# STM32F103-260914.net
KiCad netlist of a schematic drawn in EasyEDA Pro
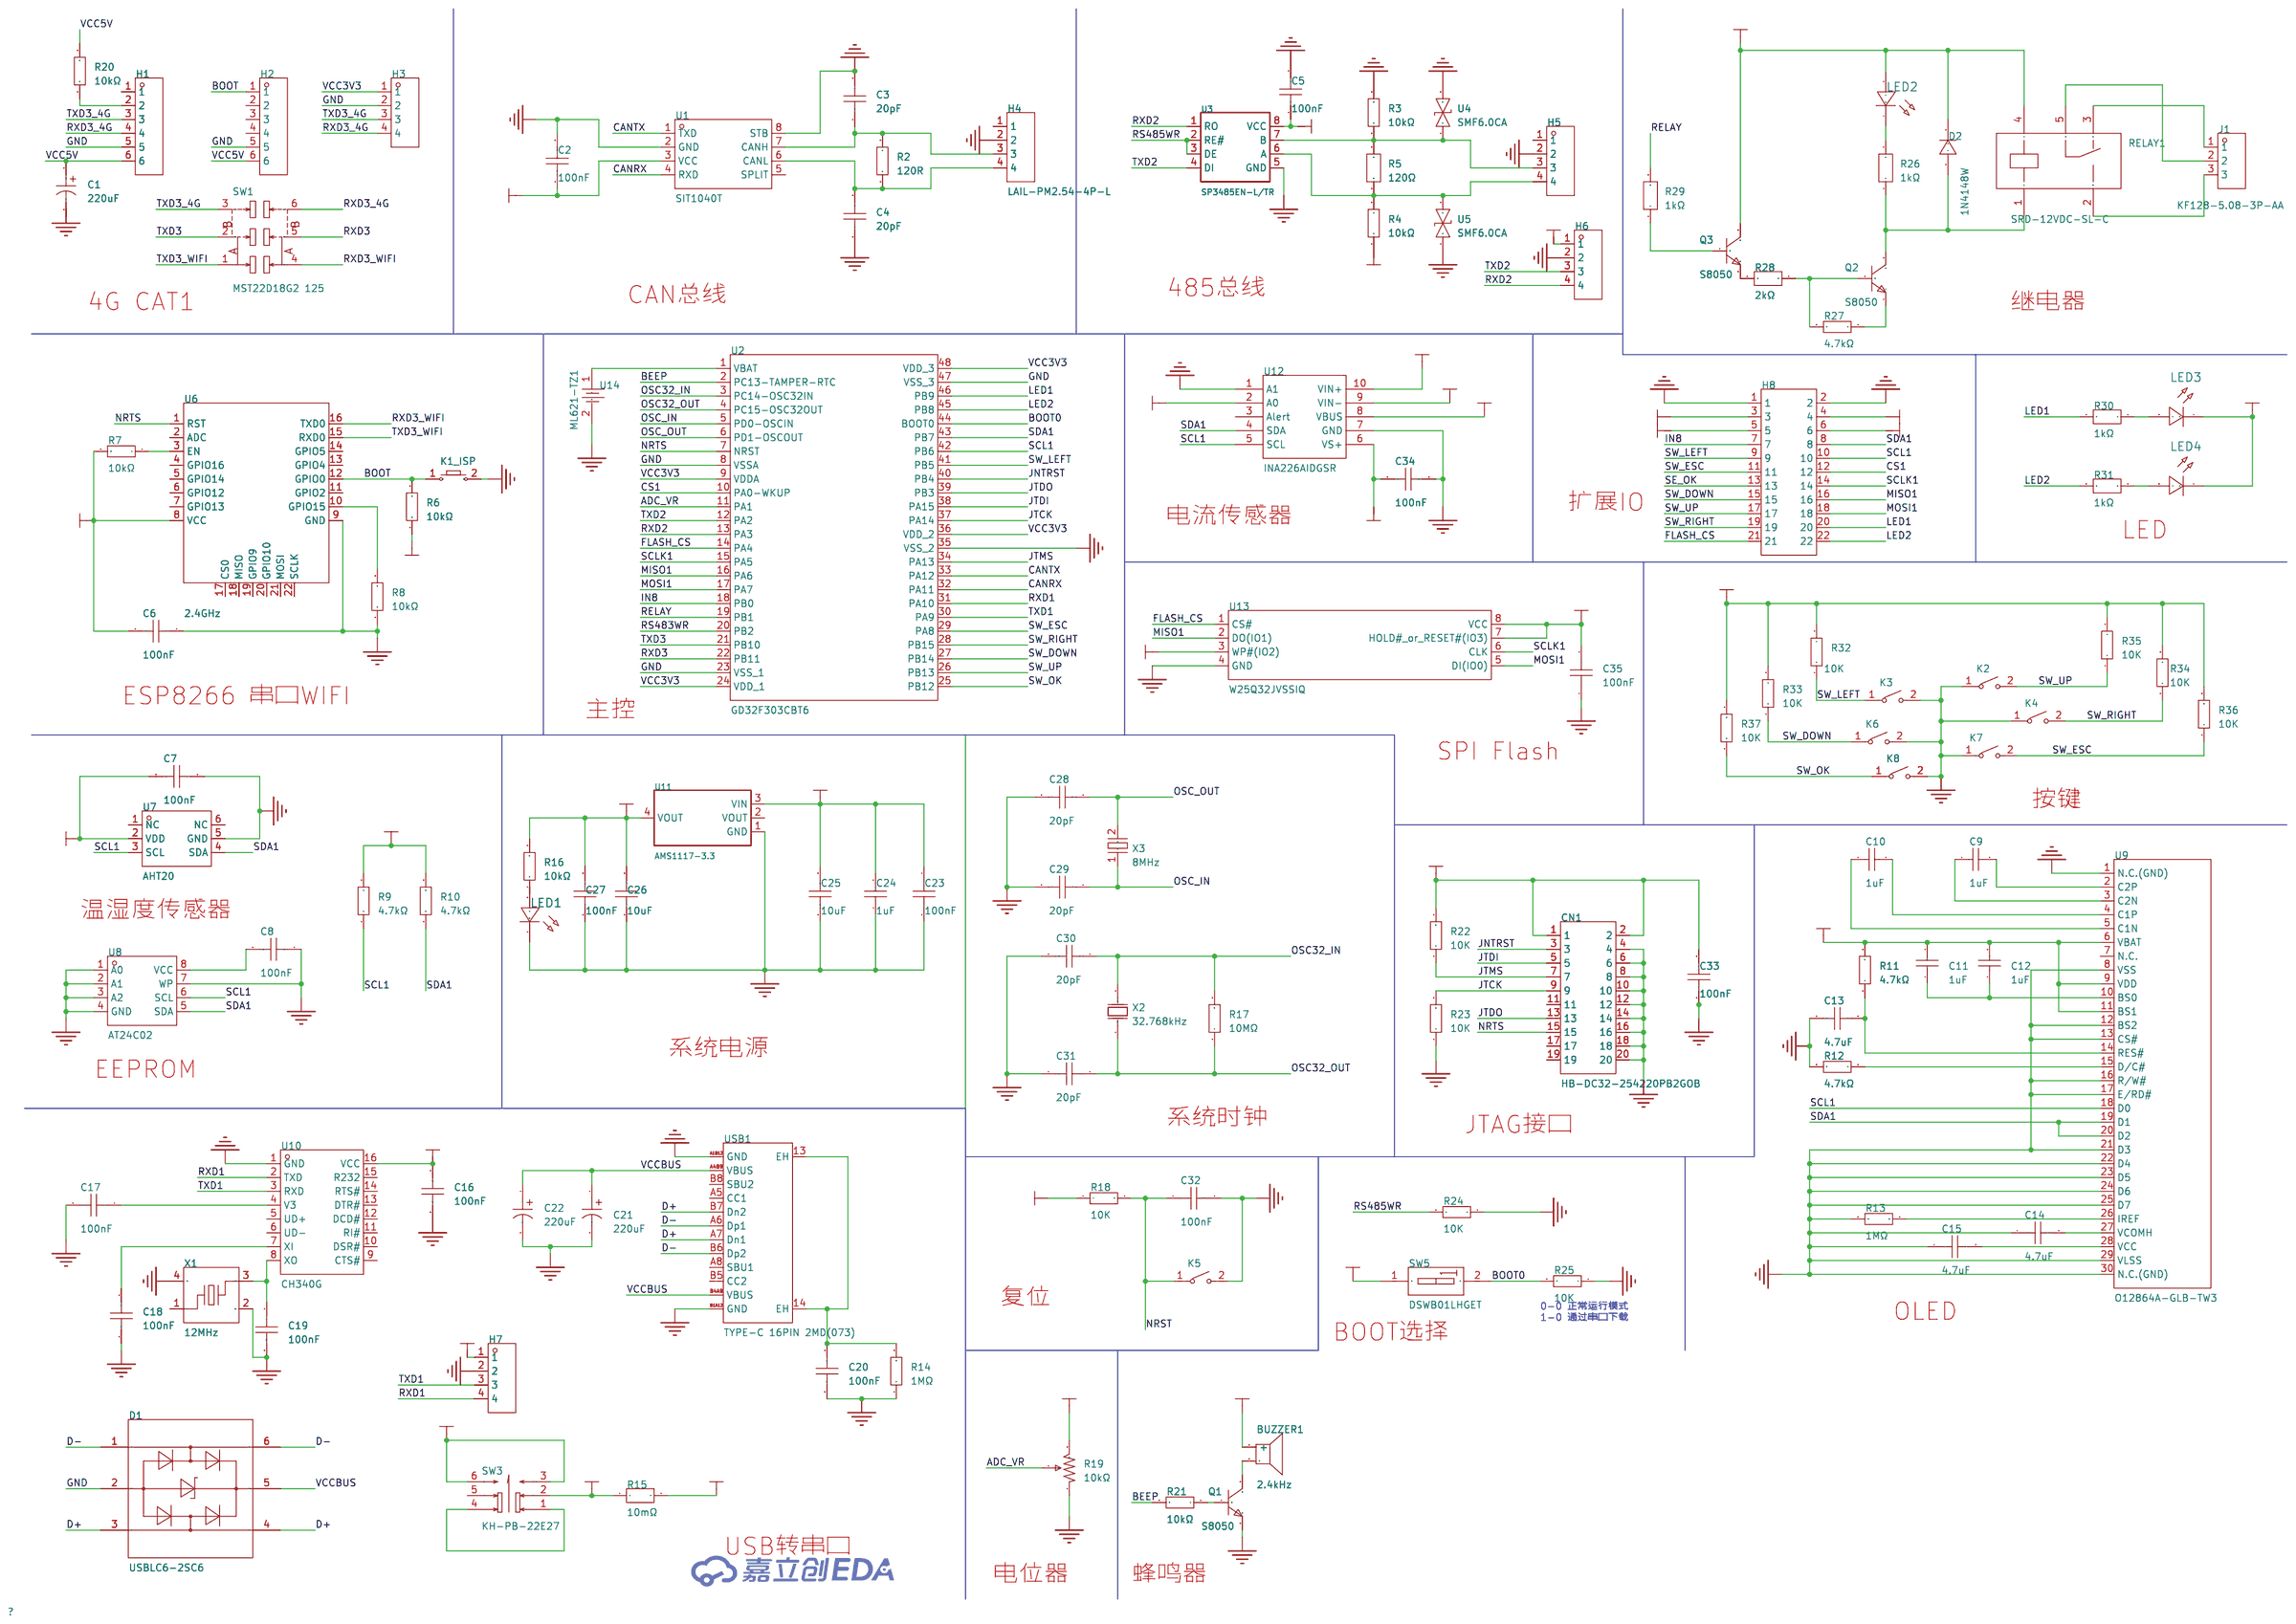
[diagram p0: schematic sheet]

(export (version "E")
  (design (tool "Eeschema 10.0.6"))
  (components
    (comp (ref "BUZZER1")
      (value "2.4kHz")
      (footprint "easyedapro:BUZ-TH_BD12.0-P7.60-D0.6-FD")
      (description "驱动方式:有源(内含驱动线路);构造类型:电磁式;额定电压:5V;频率:2.4kHz;声压(SPL):85dB;")
      (fields (field (name "Manufacturer Part") "TMB12A05") (field (name "Manufacturer") "华能"))
      (libsource (lib "easyedapro") (part "TMB12A05"))
    )
    (comp (ref "C1")
      (value "220uF")
      (footprint "easyedapro:CAP-SMD_BD6.3-L6.6-W6.6-FD")
      (description "容值:220uF;精度:±20%;额定电压:35V;纹波电流:190mA@120Hz;")
      (fields (field (name "Manufacturer Part") "JVJ35V220M6x8") (field (name "Manufacturer") "JIERR(捷而瑞)"))
      (libsource (lib "easyedapro") (part "JVJ35V220M6X8"))
    )
    (comp (ref "C2")
      (value "100nF")
      (footprint "easyedapro:C0805")
      (libsource (lib "easyedapro") (part "Capacitance"))
    )
    (comp (ref "C3")
      (value "20pF")
      (footprint "easyedapro:C0805")
      (libsource (lib "easyedapro") (part "Capacitance"))
    )
    (comp (ref "C4")
      (value "20pF")
      (footprint "easyedapro:C0805")
      (libsource (lib "easyedapro") (part "Capacitance"))
    )
    (comp (ref "C5")
      (value "100nF")
      (footprint "easyedapro:C0603")
      (description "容值:100nF;精度:±10%;额定电压:100V;温度系数:X7R;")
      (fields
        (field (name "Manufacturer Part") "CC0603KRX7R0BB104")
        (field (name "Manufacturer") "YAGEO(国巨)")
      )
      (libsource (lib "easyedapro") (part "CC0603KRX7R0BB104"))
    )
    (comp (ref "C6")
      (value "100nF")
      (footprint "easyedapro:C0603")
      (description "容值:100nF;精度:±10%;额定电压:100V;温度系数:X7R;")
      (fields
        (field (name "Manufacturer Part") "CC0603KRX7R0BB104")
        (field (name "Manufacturer") "YAGEO(国巨)")
      )
      (libsource (lib "easyedapro") (part "CC0603KRX7R0BB104"))
    )
    (comp (ref "C7")
      (value "100nF")
      (footprint "easyedapro:C0603")
      (description "容值:100nF;精度:±10%;额定电压:100V;温度系数:X7R;")
      (fields
        (field (name "Manufacturer Part") "CC0603KRX7R0BB104")
        (field (name "Manufacturer") "YAGEO(国巨)")
      )
      (libsource (lib "easyedapro") (part "CC0603KRX7R0BB104"))
    )
    (comp (ref "C8")
      (value "100nF")
      (footprint "easyedapro:C0603")
      (description "容值:100nF;精度:±10%;额定电压:100V;温度系数:X7R;")
      (fields
        (field (name "Manufacturer Part") "CC0603KRX7R0BB104")
        (field (name "Manufacturer") "YAGEO(国巨)")
      )
      (libsource (lib "easyedapro") (part "CC0603KRX7R0BB104"))
    )
    (comp (ref "C9")
      (value "1uF")
      (footprint "easyedapro:C0603")
      (description "容值:1uF;精度:±10%;额定电压:25V;温度系数:X5R;")
      (fields
        (field (name "Manufacturer Part") "CC0603KRX5R8BB105")
        (field (name "Manufacturer") "YAGEO(国巨)")
      )
      (libsource (lib "easyedapro") (part "CC0603KRX5R8BB105"))
    )
    (comp (ref "C10")
      (value "1uF")
      (footprint "easyedapro:C0603")
      (description "容值:1uF;精度:±10%;额定电压:25V;温度系数:X5R;")
      (fields
        (field (name "Manufacturer Part") "CC0603KRX5R8BB105")
        (field (name "Manufacturer") "YAGEO(国巨)")
      )
      (libsource (lib "easyedapro") (part "CC0603KRX5R8BB105"))
    )
    (comp (ref "C11")
      (value "1uF")
      (footprint "easyedapro:C0603")
      (description "容值:1uF;精度:±10%;额定电压:25V;温度系数:X5R;")
      (fields
        (field (name "Manufacturer Part") "CC0603KRX5R8BB105")
        (field (name "Manufacturer") "YAGEO(国巨)")
      )
      (libsource (lib "easyedapro") (part "CC0603KRX5R8BB105"))
    )
    (comp (ref "C12")
      (value "1uF")
      (footprint "easyedapro:C0603")
      (description "容值:1uF;精度:±10%;额定电压:25V;温度系数:X5R;")
      (fields
        (field (name "Manufacturer Part") "CC0603KRX5R8BB105")
        (field (name "Manufacturer") "YAGEO(国巨)")
      )
      (libsource (lib "easyedapro") (part "CC0603KRX5R8BB105"))
    )
    (comp (ref "C13")
      (value "4.7uF")
      (footprint "easyedapro:C0603")
      (description "容值:4.7uF;精度:±10%;额定电压:16V;温度系数:X5R;")
      (fields
        (field (name "Manufacturer Part") "CL10A475KO8NNNC")
        (field (name "Manufacturer") "SAMSUNG(三星)")
      )
      (libsource (lib "easyedapro") (part "CL10A475KO8NNNC"))
    )
    (comp (ref "C14")
      (value "4.7uF")
      (footprint "easyedapro:C0603")
      (description "容值:4.7uF;精度:±10%;额定电压:16V;温度系数:X5R;")
      (fields
        (field (name "Manufacturer Part") "CL10A475KO8NNNC")
        (field (name "Manufacturer") "SAMSUNG(三星)")
      )
      (libsource (lib "easyedapro") (part "CL10A475KO8NNNC"))
    )
    (comp (ref "C15")
      (value "4.7uF")
      (footprint "easyedapro:C0603")
      (description "容值:4.7uF;精度:±10%;额定电压:16V;温度系数:X5R;")
      (fields
        (field (name "Manufacturer Part") "CL10A475KO8NNNC")
        (field (name "Manufacturer") "SAMSUNG(三星)")
      )
      (libsource (lib "easyedapro") (part "CL10A475KO8NNNC"))
    )
    (comp (ref "C16")
      (value "100nF")
      (footprint "easyedapro:C0603")
      (description "容值:100nF;精度:±10%;额定电压:100V;温度系数:X7R;")
      (fields
        (field (name "Manufacturer Part") "CC0603KRX7R0BB104")
        (field (name "Manufacturer") "YAGEO(国巨)")
      )
      (libsource (lib "easyedapro") (part "CC0603KRX7R0BB104"))
    )
    (comp (ref "C17")
      (value "100nF")
      (footprint "easyedapro:C0603")
      (description "容值:100nF;精度:±10%;额定电压:100V;温度系数:X7R;")
      (fields
        (field (name "Manufacturer Part") "CC0603KRX7R0BB104")
        (field (name "Manufacturer") "YAGEO(国巨)")
      )
      (libsource (lib "easyedapro") (part "CC0603KRX7R0BB104"))
    )
    (comp (ref "C18")
      (value "100nF")
      (footprint "easyedapro:C0603")
      (description "容值:100nF;精度:±10%;额定电压:100V;温度系数:X7R;")
      (fields
        (field (name "Manufacturer Part") "CC0603KRX7R0BB104")
        (field (name "Manufacturer") "YAGEO(国巨)")
      )
      (libsource (lib "easyedapro") (part "CC0603KRX7R0BB104"))
    )
    (comp (ref "C19")
      (value "100nF")
      (footprint "easyedapro:C0603")
      (description "容值:100nF;精度:±10%;额定电压:100V;温度系数:X7R;")
      (fields
        (field (name "Manufacturer Part") "CC0603KRX7R0BB104")
        (field (name "Manufacturer") "YAGEO(国巨)")
      )
      (libsource (lib "easyedapro") (part "CC0603KRX7R0BB104"))
    )
    (comp (ref "C20")
      (value "100nF")
      (footprint "easyedapro:C0603")
      (description "容值:100nF;精度:±10%;额定电压:100V;温度系数:X7R;")
      (fields
        (field (name "Manufacturer Part") "CC0603KRX7R0BB104")
        (field (name "Manufacturer") "YAGEO(国巨)")
      )
      (libsource (lib "easyedapro") (part "CC0603KRX7R0BB104"))
    )
    (comp (ref "C21")
      (value "220uF")
      (footprint "easyedapro:CAP-SMD_BD6.3-L6.6-W6.6-FD")
      (description "容值:220uF;精度:±20%;额定电压:35V;纹波电流:600mA@100kHz;等效串联电阻(ESR):160mΩ@100kHz;")
      (fields (field (name "Manufacturer Part") "189RV0019") (field (name "Manufacturer") "KNSCHA(科尼盛)"))
      (libsource (lib "easyedapro") (part "189RV0019"))
    )
    (comp (ref "C22")
      (value "220uF")
      (footprint "easyedapro:CAP-SMD_BD6.3-L6.6-W6.6-FD")
      (description "容值:220uF;精度:±20%;额定电压:35V;纹波电流:600mA@100kHz;等效串联电阻(ESR):160mΩ@100kHz;")
      (fields (field (name "Manufacturer Part") "189RV0019") (field (name "Manufacturer") "KNSCHA(科尼盛)"))
      (libsource (lib "easyedapro") (part "189RV0019"))
    )
    (comp (ref "C23")
      (value "100nF")
      (footprint "easyedapro:C0603")
      (description "容值:100nF;精度:±10%;额定电压:100V;温度系数:X7R;")
      (fields
        (field (name "Manufacturer Part") "CC0603KRX7R0BB104")
        (field (name "Manufacturer") "YAGEO(国巨)")
      )
      (libsource (lib "easyedapro") (part "CC0603KRX7R0BB104"))
    )
    (comp (ref "C24")
      (value "1uF")
      (footprint "easyedapro:C0603")
      (description "容值:1uF;精度:±10%;额定电压:25V;温度系数:X5R;")
      (fields
        (field (name "Manufacturer Part") "CC0603KRX5R8BB105")
        (field (name "Manufacturer") "YAGEO(国巨)")
      )
      (libsource (lib "easyedapro") (part "CC0603KRX5R8BB105"))
    )
    (comp (ref "C25")
      (value "10uF")
      (footprint "easyedapro:C0603")
      (description "容值:10uF;精度:±20%;额定电压:25V;温度系数:X5R;")
      (fields
        (field (name "Manufacturer Part") "CL10A106MA8NRNC")
        (field (name "Manufacturer") "SAMSUNG(三星)")
      )
      (libsource (lib "easyedapro") (part "CL10A106MA8NRNC"))
    )
    (comp (ref "C26")
      (value "10uF")
      (footprint "easyedapro:C0603")
      (description "容值:10uF;精度:±20%;额定电压:25V;温度系数:X5R;")
      (fields
        (field (name "Manufacturer Part") "CL10A106MA8NRNC")
        (field (name "Manufacturer") "SAMSUNG(三星)")
      )
      (libsource (lib "easyedapro") (part "CL10A106MA8NRNC"))
    )
    (comp (ref "C27")
      (value "100nF")
      (footprint "easyedapro:C0603")
      (description "容值:100nF;精度:±10%;额定电压:100V;温度系数:X7R;")
      (fields
        (field (name "Manufacturer Part") "CC0603KRX7R0BB104")
        (field (name "Manufacturer") "YAGEO(国巨)")
      )
      (libsource (lib "easyedapro") (part "CC0603KRX7R0BB104"))
    )
    (comp (ref "C28")
      (value "20pF")
      (footprint "easyedapro:C0805")
      (libsource (lib "easyedapro") (part "Capacitance"))
    )
    (comp (ref "C29")
      (value "20pF")
      (footprint "easyedapro:C0805")
      (libsource (lib "easyedapro") (part "Capacitance"))
    )
    (comp (ref "C30")
      (value "20pF")
      (footprint "easyedapro:C0805")
      (libsource (lib "easyedapro") (part "Capacitance"))
    )
    (comp (ref "C31")
      (value "20pF")
      (footprint "easyedapro:C0805")
      (libsource (lib "easyedapro") (part "Capacitance"))
    )
    (comp (ref "C32")
      (value "100nF")
      (footprint "easyedapro:C0603")
      (description "容值:100nF;精度:±10%;额定电压:100V;温度系数:X7R;")
      (fields
        (field (name "Manufacturer Part") "CC0603KRX7R0BB104")
        (field (name "Manufacturer") "YAGEO(国巨)")
      )
      (libsource (lib "easyedapro") (part "CC0603KRX7R0BB104"))
    )
    (comp (ref "C33")
      (value "100nF")
      (footprint "easyedapro:C0603")
      (description "容值:100nF;精度:±10%;额定电压:100V;温度系数:X7R;")
      (fields
        (field (name "Manufacturer Part") "CC0603KRX7R0BB104")
        (field (name "Manufacturer") "YAGEO(国巨)")
      )
      (libsource (lib "easyedapro") (part "CC0603KRX7R0BB104"))
    )
    (comp (ref "C34")
      (value "100nF")
      (footprint "easyedapro:C0603")
      (description "容值:100nF;精度:±10%;额定电压:100V;温度系数:X7R;")
      (fields
        (field (name "Manufacturer Part") "CC0603KRX7R0BB104")
        (field (name "Manufacturer") "YAGEO(国巨)")
      )
      (libsource (lib "easyedapro") (part "CC0603KRX7R0BB104"))
    )
    (comp (ref "C35")
      (value "100nF")
      (footprint "easyedapro:C0603")
      (description "容值:100nF;精度:±10%;额定电压:100V;温度系数:X7R;")
      (fields
        (field (name "Manufacturer Part") "CC0603KRX7R0BB104")
        (field (name "Manufacturer") "YAGEO(国巨)")
      )
      (libsource (lib "easyedapro") (part "CC0603KRX7R0BB104"))
    )
    (comp (ref "CN1")
      (value "HB-DC32-254220PB2GOB")
      (footprint "easyedapro:CONN-TH-20P_HB-DC32-254220PB2GOB")
      (fields (field (name "Manufacturer") "HANBO(汉博)"))
      (libsource (lib "easyedapro") (part "HB-DC32-254220PB2GOB"))
    )
    (comp (ref "D1")
      (value "USBLC6-2SC6")
      (footprint "easyedapro:SOT-23-6_L2.9-W1.6-P0.95-LS2.8-BL")
      (description "极性:单向;反向截止电压(Vrwm):5.25V;钳位电压:17V;峰值脉冲电流(Ipp):5A;击穿电压(VBR):6V;")
      (fields (field (name "Manufacturer") "ST(意法半导体)"))
      (libsource (lib "easyedapro") (part "USBLC6-2SC6"))
    )
    (comp (ref "D2")
      (value "1N4148W")
      (footprint "easyedapro:SOD-123F_L2.7-W1.6-LS3.8-RD")
      (description "二极管配置:独立式;正向压降(Vf):1V@50mA;直流反向耐压(Vr):75V;整流电流:150mA;反向恢复时间(Trr):4ns;")
      (fields (field (name "Manufacturer") "ST(先科)"))
      (libsource (lib "easyedapro") (part "1N4148W_C81598"))
    )
    (comp (ref "H1")
      (value "~")
      (footprint "easyedapro:HDR-TH_6P-P2.54-V-F")
      (libsource (lib "easyedapro") (part "Header-Female-2.54_1x6"))
    )
    (comp (ref "H2")
      (value "~")
      (footprint "easyedapro:HDR-TH_6P-P2.54-V-F")
      (libsource (lib "easyedapro") (part "Header-Female-2.54_1x6"))
    )
    (comp (ref "H3")
      (value "~")
      (footprint "easyedapro:HDR-TH_4P-P2.54-V-F")
      (libsource (lib "easyedapro") (part "2.54-1*4P母"))
    )
    (comp (ref "H4")
      (value "LAIL-PM2.54-4P-L")
      (footprint "easyedapro:HDR-TH_4P-P2.54-V-M")
      (fields (field (name "Manufacturer") "LAILAN(莱联)"))
      (libsource (lib "easyedapro") (part "PZ254V-11-04P"))
    )
    (comp (ref "H5")
      (value "PM254V-11-04-H85")
      (footprint "easyedapro:HDR-TH_4P-P2.54-V-F")
      (fields (field (name "Manufacturer") "XFCN(兴飞)"))
      (libsource (lib "easyedapro") (part "2.54-1*4P母"))
    )
    (comp (ref "H6")
      (value "~")
      (footprint "easyedapro:HDR-TH_4P-P2.54-V-F")
      (libsource (lib "easyedapro") (part "2.54-1*4P母"))
    )
    (comp (ref "H7")
      (value "~")
      (footprint "easyedapro:HDR-TH_4P-P2.54-V-F")
      (libsource (lib "easyedapro") (part "2.54-1*4P母"))
    )
    (comp (ref "H8")
      (value "PZ254V-12-22P")
      (footprint "easyedapro:HDR-TH_22P-P2.54-V-M-R2-C11-S2.54")
      (fields (field (name "Manufacturer") "XFCN(兴飞)"))
      (libsource (lib "easyedapro") (part "PZ254V-12-22P"))
    )
    (comp (ref "J1")
      (value "KF128-5.08-3P-AA")
      (footprint "easyedapro:CONN-TH_3P-P5.08_KF128-5.08-3P")
      (fields (field (name "Manufacturer") "KEFA(科发)"))
      (libsource (lib "easyedapro") (part "KF128-5.08-3P"))
    )
    (comp (ref "K1_ISP")
      (value "KH-6X6X5H-STM")
      (footprint "easyedapro:Key_SMD_3x4x2")
      (fields (field (name "Manufacturer") "kinghelm(金航标)"))
      (libsource (lib "easyedapro") (part "轻触按键x2"))
    )
    (comp (ref "K2")
      (value "TS-1088R-02026")
      (footprint "easyedapro:SW-SMD_L3.9-W3.0-P4.45")
      (fields (field (name "Manufacturer") "XUNPU(讯普)"))
      (libsource (lib "easyedapro") (part "TS-1088R-02026"))
    )
    (comp (ref "K3")
      (value "TS-1088R-02026")
      (footprint "easyedapro:SW-SMD_L3.9-W3.0-P4.45")
      (fields (field (name "Manufacturer") "XUNPU(讯普)"))
      (libsource (lib "easyedapro") (part "TS-1088R-02026"))
    )
    (comp (ref "K4")
      (value "TS-1088R-02026")
      (footprint "easyedapro:SW-SMD_L3.9-W3.0-P4.45")
      (fields (field (name "Manufacturer") "XUNPU(讯普)"))
      (libsource (lib "easyedapro") (part "TS-1088R-02026"))
    )
    (comp (ref "K5")
      (value "TS-1088R-02026")
      (footprint "easyedapro:SW-SMD_L3.9-W3.0-P4.45")
      (fields (field (name "Manufacturer") "XUNPU(讯普)"))
      (libsource (lib "easyedapro") (part "TS-1088R-02026"))
    )
    (comp (ref "K6")
      (value "TS-1088R-02026")
      (footprint "easyedapro:SW-SMD_L3.9-W3.0-P4.45")
      (fields (field (name "Manufacturer") "XUNPU(讯普)"))
      (libsource (lib "easyedapro") (part "TS-1088R-02026"))
    )
    (comp (ref "K7")
      (value "TS-1088R-02026")
      (footprint "easyedapro:SW-SMD_L3.9-W3.0-P4.45")
      (fields (field (name "Manufacturer") "XUNPU(讯普)"))
      (libsource (lib "easyedapro") (part "TS-1088R-02026"))
    )
    (comp (ref "K8")
      (value "TS-1088R-02026")
      (footprint "easyedapro:SW-SMD_L3.9-W3.0-P4.45")
      (fields (field (name "Manufacturer") "XUNPU(讯普)"))
      (libsource (lib "easyedapro") (part "TS-1088R-02026"))
    )
    (comp (ref "LED1")
      (value "~")
      (footprint "easyedapro:LED_0603")
      (libsource (lib "easyedapro") (part "LED_R"))
    )
    (comp (ref "LED2")
      (value "~")
      (footprint "easyedapro:LED_0603")
      (libsource (lib "easyedapro") (part "LED_R"))
    )
    (comp (ref "LED3")
      (value "~")
      (footprint "easyedapro:LED_0603")
      (libsource (lib "easyedapro") (part "LED_R"))
    )
    (comp (ref "LED4")
      (value "~")
      (footprint "easyedapro:LED_0603")
      (libsource (lib "easyedapro") (part "LED_R"))
    )
    (comp (ref "Q1")
      (value "S8050")
      (footprint "easyedapro:SOT-23-3_L2.9-W1.3-P1.90-LS2.3-BR")
      (description "晶体管类型:NPN;集电极电流(Ic):500mA;集射极击穿电压(Vceo):25V;耗散功率(Pd):300mW;直流电流增益(hFE):120;")
      (fields (field (name "Manufacturer") "R+O(宏嘉诚)"))
      (libsource (lib "easyedapro") (part "S8050_C20069125"))
    )
    (comp (ref "Q2")
      (value "S8050")
      (footprint "easyedapro:SOT-23-3_L2.9-W1.3-P1.90-LS2.3-BR")
      (description "晶体管类型:NPN;集电极电流(Ic):500mA;集射极击穿电压(Vceo):25V;耗散功率(Pd):300mW;直流电流增益(hFE):120;")
      (fields (field (name "Manufacturer") "R+O(宏嘉诚)"))
      (libsource (lib "easyedapro") (part "S8050_C20069125"))
    )
    (comp (ref "Q3")
      (value "S8050")
      (footprint "easyedapro:SOT-23-3_L2.9-W1.3-P1.90-LS2.3-BR")
      (description "晶体管类型:NPN;集电极电流(Ic):500mA;集射极击穿电压(Vceo):25V;耗散功率(Pd):300mW;直流电流增益(hFE):120;")
      (fields (field (name "Manufacturer") "R+O(宏嘉诚)"))
      (libsource (lib "easyedapro") (part "S8050_C20069125"))
    )
    (comp (ref "R2") (value "120R") (footprint "easyedapro:R0805") (libsource (lib "easyedapro") (part "电阻")))
    (comp (ref "R3")
      (value "10kΩ")
      (footprint "easyedapro:R0603")
      (description "电阻类型:厚膜电阻;阻值:10kΩ;精度:±1%;功率:100mW;工作电压:75V;温度系数:±100ppm/°C;")
      (fields
        (field (name "Manufacturer Part") "0603WAF1002T5E")
        (field (name "Manufacturer") "UNI-ROYAL(厚声)")
      )
      (libsource (lib "easyedapro") (part "0603WAF1002T5E"))
    )
    (comp (ref "R4")
      (value "10kΩ")
      (footprint "easyedapro:R0603")
      (description "电阻类型:厚膜电阻;阻值:10kΩ;精度:±1%;功率:100mW;工作电压:75V;温度系数:±100ppm/°C;")
      (fields
        (field (name "Manufacturer Part") "0603WAF1002T5E")
        (field (name "Manufacturer") "UNI-ROYAL(厚声)")
      )
      (libsource (lib "easyedapro") (part "0603WAF1002T5E"))
    )
    (comp (ref "R5")
      (value "120Ω")
      (footprint "easyedapro:R1206")
      (description "电阻类型:厚膜电阻;阻值:120Ω;精度:±1%;功率:250mW;工作电压:200V;温度系数:±100ppm/°C;")
      (fields (field (name "Manufacturer Part") "FRC1206F1200TS") (field (name "Manufacturer") "FOJAN(富捷)"))
      (libsource (lib "easyedapro") (part "FRC1206F1200TS"))
    )
    (comp (ref "R6")
      (value "10kΩ")
      (footprint "easyedapro:R0603")
      (description "电阻类型:厚膜电阻;阻值:10kΩ;精度:±1%;功率:100mW;工作电压:75V;温度系数:±100ppm/°C;")
      (fields
        (field (name "Manufacturer Part") "0603WAF1002T5E")
        (field (name "Manufacturer") "UNI-ROYAL(厚声)")
      )
      (libsource (lib "easyedapro") (part "0603WAF1002T5E"))
    )
    (comp (ref "R7")
      (value "10kΩ")
      (footprint "easyedapro:R0603")
      (description "电阻类型:厚膜电阻;阻值:10kΩ;精度:±1%;功率:100mW;工作电压:75V;温度系数:±100ppm/°C;")
      (fields
        (field (name "Manufacturer Part") "0603WAF1002T5E")
        (field (name "Manufacturer") "UNI-ROYAL(厚声)")
      )
      (libsource (lib "easyedapro") (part "0603WAF1002T5E"))
    )
    (comp (ref "R8")
      (value "10kΩ")
      (footprint "easyedapro:R0603")
      (description "电阻类型:厚膜电阻;阻值:10kΩ;精度:±1%;功率:100mW;工作电压:75V;温度系数:±100ppm/°C;")
      (fields
        (field (name "Manufacturer Part") "0603WAF1002T5E")
        (field (name "Manufacturer") "UNI-ROYAL(厚声)")
      )
      (libsource (lib "easyedapro") (part "0603WAF1002T5E"))
    )
    (comp (ref "R9")
      (value "4.7kΩ")
      (footprint "easyedapro:R0402")
      (description "电阻类型:厚膜电阻;阻值:4.7kΩ;精度:±1%;功率:62.5mW;工作电压:50V;温度系数:±100ppm/°C;")
      (fields (field (name "Manufacturer Part") "RC0402FR-074K7L") (field (name "Manufacturer") "YAGEO(国巨)"))
      (libsource (lib "easyedapro") (part "RC0402FR-074K7L"))
    )
    (comp (ref "R10")
      (value "4.7kΩ")
      (footprint "easyedapro:R0402")
      (description "电阻类型:厚膜电阻;阻值:4.7kΩ;精度:±1%;功率:62.5mW;工作电压:50V;温度系数:±100ppm/°C;")
      (fields (field (name "Manufacturer Part") "RC0402FR-074K7L") (field (name "Manufacturer") "YAGEO(国巨)"))
      (libsource (lib "easyedapro") (part "RC0402FR-074K7L"))
    )
    (comp (ref "R11")
      (value "4.7kΩ")
      (footprint "easyedapro:R0402")
      (description "电阻类型:厚膜电阻;阻值:4.7kΩ;精度:±1%;功率:62.5mW;工作电压:50V;温度系数:±100ppm/°C;")
      (fields (field (name "Manufacturer Part") "RC0402FR-074K7L") (field (name "Manufacturer") "YAGEO(国巨)"))
      (libsource (lib "easyedapro") (part "RC0402FR-074K7L"))
    )
    (comp (ref "R12")
      (value "4.7kΩ")
      (footprint "easyedapro:R0402")
      (description "电阻类型:厚膜电阻;阻值:4.7kΩ;精度:±1%;功率:62.5mW;工作电压:50V;温度系数:±100ppm/°C;")
      (fields (field (name "Manufacturer Part") "RC0402FR-074K7L") (field (name "Manufacturer") "YAGEO(国巨)"))
      (libsource (lib "easyedapro") (part "RC0402FR-074K7L"))
    )
    (comp (ref "R13")
      (value "1MΩ")
      (footprint "easyedapro:R0603")
      (description "电阻类型:厚膜电阻;阻值:1MΩ;精度:±1%;功率:100mW;工作电压:75V;温度系数:±100ppm/°C;")
      (fields
        (field (name "Manufacturer Part") "0603WAF1004T5E")
        (field (name "Manufacturer") "UNI-ROYAL(厚声)")
      )
      (libsource (lib "easyedapro") (part "0603WAF1004T5E"))
    )
    (comp (ref "R14")
      (value "1MΩ")
      (footprint "easyedapro:R0603")
      (description "电阻类型:厚膜电阻;阻值:1MΩ;精度:±1%;功率:100mW;工作电压:75V;温度系数:±100ppm/°C;")
      (fields
        (field (name "Manufacturer Part") "0603WAF1004T5E")
        (field (name "Manufacturer") "UNI-ROYAL(厚声)")
      )
      (libsource (lib "easyedapro") (part "0603WAF1004T5E"))
    )
    (comp (ref "R15")
      (value "10mΩ")
      (footprint "easyedapro:R2512")
      (description "电阻类型:采样电阻；合金电阻;阻值:10mΩ;精度:±1%;功率:3W;温度系数:±50ppm/°C;安装方式:贴片;")
      (fields (field (name "Manufacturer Part") "RE2512F3R010") (field (name "Manufacturer") "JIERR(捷而瑞)"))
      (libsource (lib "easyedapro") (part "RE2512F3R010"))
    )
    (comp (ref "R16")
      (value "10kΩ")
      (footprint "easyedapro:R0603")
      (description "电阻类型:厚膜电阻;阻值:10kΩ;精度:±1%;功率:100mW;工作电压:75V;温度系数:±100ppm/°C;")
      (fields
        (field (name "Manufacturer Part") "0603WAF1002T5E")
        (field (name "Manufacturer") "UNI-ROYAL(厚声)")
      )
      (libsource (lib "easyedapro") (part "0603WAF1002T5E"))
    )
    (comp (ref "R17")
      (value "10MΩ")
      (footprint "easyedapro:R0603")
      (description "电阻类型:厚膜电阻;阻值:1MΩ;精度:±1%;功率:100mW;工作电压:75V;温度系数:±100ppm/°C;")
      (fields
        (field (name "Manufacturer Part") "0603WAF1004T5E")
        (field (name "Manufacturer") "UNI-ROYAL(厚声)")
      )
      (libsource (lib "easyedapro") (part "0603WAF1004T5E"))
    )
    (comp (ref "R18") (value "10K") (footprint "easyedapro:R0805") (libsource (lib "easyedapro") (part "电阻")))
    (comp (ref "R19")
      (value "10kΩ")
      (footprint "easyedapro:RES-ADJ-TH_3362P")
      (description "阻值:10kΩ;精度:±10%;功率:500mW;温度系数:±250ppm/°C;")
      (fields (field (name "Manufacturer Part") "3362P-1-103") (field (name "Manufacturer") "JIERR(捷而瑞)"))
      (libsource (lib "easyedapro") (part "3362P-1-103_C48997914"))
    )
    (comp (ref "R20")
      (value "10kΩ")
      (footprint "easyedapro:R0603")
      (description "电阻类型:厚膜电阻;阻值:10kΩ;精度:±1%;功率:100mW;工作电压:75V;温度系数:±100ppm/°C;")
      (fields
        (field (name "Manufacturer Part") "0603WAF1002T5E")
        (field (name "Manufacturer") "UNI-ROYAL(厚声)")
      )
      (libsource (lib "easyedapro") (part "0603WAF1002T5E"))
    )
    (comp (ref "R21")
      (value "10kΩ")
      (footprint "easyedapro:R0603")
      (description "电阻类型:厚膜电阻;阻值:10kΩ;精度:±1%;功率:100mW;工作电压:75V;温度系数:±100ppm/°C;")
      (fields
        (field (name "Manufacturer Part") "0603WAF1002T5E")
        (field (name "Manufacturer") "UNI-ROYAL(厚声)")
      )
      (libsource (lib "easyedapro") (part "0603WAF1002T5E"))
    )
    (comp (ref "R22") (value "10K") (footprint "easyedapro:R0805") (libsource (lib "easyedapro") (part "电阻")))
    (comp (ref "R23") (value "10K") (footprint "easyedapro:R0805") (libsource (lib "easyedapro") (part "电阻")))
    (comp (ref "R24") (value "10K") (footprint "easyedapro:R0805") (libsource (lib "easyedapro") (part "电阻")))
    (comp (ref "R25") (value "10K") (footprint "easyedapro:R0805") (libsource (lib "easyedapro") (part "电阻")))
    (comp (ref "R26")
      (value "1kΩ")
      (footprint "easyedapro:R0603")
      (description "电阻类型:薄膜电阻;阻值:1kΩ;精度:±0.1%;功率:100mW;工作电压:100V;温度系数:±10ppm/°C;")
      (fields (field (name "Manufacturer Part") "PTFR0603B1K00N9") (field (name "Manufacturer") "RESI(开步睿思)"))
      (libsource (lib "easyedapro") (part "PTFR0603B1K00N9"))
    )
    (comp (ref "R27")
      (value "4.7kΩ")
      (footprint "easyedapro:R0402")
      (description "电阻类型:厚膜电阻;阻值:4.7kΩ;精度:±1%;功率:62.5mW;工作电压:50V;温度系数:±100ppm/°C;")
      (fields (field (name "Manufacturer Part") "RC0402FR-074K7L") (field (name "Manufacturer") "YAGEO(国巨)"))
      (libsource (lib "easyedapro") (part "RC0402FR-074K7L"))
    )
    (comp (ref "R28")
      (value "2kΩ")
      (footprint "easyedapro:R0603")
      (description "电阻类型:薄膜电阻;阻值:1kΩ;精度:±0.1%;功率:100mW;工作电压:100V;温度系数:±10ppm/°C;")
      (fields (field (name "Manufacturer Part") "PTFR0603B1K00N9") (field (name "Manufacturer") "RESI(开步睿思)"))
      (libsource (lib "easyedapro") (part "PTFR0603B1K00N9"))
    )
    (comp (ref "R29")
      (value "1kΩ")
      (footprint "easyedapro:R0603")
      (description "电阻类型:薄膜电阻;阻值:1kΩ;精度:±0.1%;功率:100mW;工作电压:100V;温度系数:±10ppm/°C;")
      (fields (field (name "Manufacturer Part") "PTFR0603B1K00N9") (field (name "Manufacturer") "RESI(开步睿思)"))
      (libsource (lib "easyedapro") (part "PTFR0603B1K00N9"))
    )
    (comp (ref "R30")
      (value "1kΩ")
      (footprint "easyedapro:R0603")
      (description "电阻类型:薄膜电阻;阻值:1kΩ;精度:±0.1%;功率:100mW;工作电压:100V;温度系数:±10ppm/°C;")
      (fields (field (name "Manufacturer Part") "PTFR0603B1K00N9") (field (name "Manufacturer") "RESI(开步睿思)"))
      (libsource (lib "easyedapro") (part "PTFR0603B1K00N9"))
    )
    (comp (ref "R31")
      (value "1kΩ")
      (footprint "easyedapro:R0603")
      (description "电阻类型:薄膜电阻;阻值:1kΩ;精度:±0.1%;功率:100mW;工作电压:100V;温度系数:±10ppm/°C;")
      (fields (field (name "Manufacturer Part") "PTFR0603B1K00N9") (field (name "Manufacturer") "RESI(开步睿思)"))
      (libsource (lib "easyedapro") (part "PTFR0603B1K00N9"))
    )
    (comp (ref "R32") (value "10K") (footprint "easyedapro:R0805") (libsource (lib "easyedapro") (part "电阻")))
    (comp (ref "R33") (value "10K") (footprint "easyedapro:R0805") (libsource (lib "easyedapro") (part "电阻")))
    (comp (ref "R34") (value "10K") (footprint "easyedapro:R0805") (libsource (lib "easyedapro") (part "电阻")))
    (comp (ref "R35") (value "10K") (footprint "easyedapro:R0805") (libsource (lib "easyedapro") (part "电阻")))
    (comp (ref "R36") (value "10K") (footprint "easyedapro:R0805") (libsource (lib "easyedapro") (part "电阻")))
    (comp (ref "R37") (value "10K") (footprint "easyedapro:R0805") (libsource (lib "easyedapro") (part "电阻")))
    (comp (ref "RELAY1")
      (value "SRD-12VDC-SL-C")
      (footprint "easyedapro:RELAY-TH_SRD-XXVDC-XL-C")
      (description "线圈电压:12V;触点形式:一组转换:1C(单刀双掷-转换);触点容量(电阻负载):-;最大切换电压:250V@AC;最大切换电流:15A;")
      (fields (field (name "Manufacturer") "松乐"))
      (libsource (lib "easyedapro") (part "SRD-12VDC-SL-C"))
    )
    (comp (ref "SW1")
      (value "MST22D18G2 125")
      (footprint "easyedapro:SW-SMD_MST22D18G2")
      (description "电路结构:双刀双掷;安装方式:立贴;开关颜色:黑色;额定电流:100mA;额定电压:12V;工作寿命:1万次;")
      (fields (field (name "Manufacturer") "SHOU HAN(首韩)"))
      (libsource (lib "easyedapro") (part "MST22D18G2 125"))
    )
    (comp (ref "SW3")
      (value "KH-PB-22E27")
      (footprint "easyedapro:SW-TH_6P-L7.0-W7.0-P2.00-LS5.0")
      (description "7*7*15.9H六脚自锁 PB-22E27")
      (fields (field (name "Manufacturer") "kinghelm(金航标)"))
      (libsource (lib "easyedapro") (part "KH-PB-22E27"))
    )
    (comp (ref "SW5")
      (value "DSWB01LHGET")
      (footprint "easyedapro:SW-TH_DSWB01LHGET")
      (description "类型:平拨,凸起式;电路结构:单刀单掷;开关位数:1位;工作寿命:-;颜色:红色;")
      (fields (field (name "Manufacturer") "YE"))
      (libsource (lib "easyedapro") (part "DSWB01LHGET"))
    )
    (comp (ref "U1")
      (value "SIT1040T")
      (footprint "easyedapro:SO-8_L4.9-W3.9-P1.27-LS5.9-BL")
      (description "类型:CAN收发器;数据速率:1Mbps;")
      (fields (field (name "Manufacturer") "SIT(芯力特)"))
      (libsource (lib "easyedapro") (part "SIT1040T"))
    )
    (comp (ref "U2")
      (value "GD32F303CBT6")
      (footprint "easyedapro:LQFP-48_L7.0-W7.0-P0.50-LS9.0-BL")
      (description "CPU内核:ARM Cortex-M4;CPU最大主频:120MHz;CPU位数:32 Bit;")
      (fields (field (name "Manufacturer") "GigaDevice(兆易创新)"))
      (libsource (lib "easyedapro") (part "GD32F303CBT6"))
    )
    (comp (ref "U3")
      (value "SP3485EN-L/TR")
      (footprint "easyedapro:SO-8_L4.9-W3.9-P1.27-LS6.0-BL")
      (description "类型:收发器;数据速率:14Mbps;")
      (fields (field (name "Manufacturer") "ElecSuper(静芯)"))
      (libsource (lib "easyedapro") (part "SP3485EN-L/TR_C41365340"))
    )
    (comp (ref "U4")
      (value "SMF6.0CA")
      (footprint "easyedapro:SOD-123FL_L2.8-W1.8-LS3.7-BI")
      (description "极性:双向;反向截止电压(Vrwm):6V;钳位电压:10.3V;峰值脉冲电流(Ipp):19.4A;峰值脉冲功率(Ppp):200W;击穿电压(VBR):6.67V;")
      (fields (field (name "Manufacturer") "Liown(里阳半导体)"))
      (libsource (lib "easyedapro") (part "SMF6.0CA_C2990473"))
    )
    (comp (ref "U5")
      (value "SMF6.0CA")
      (footprint "easyedapro:SOD-123FL_L2.8-W1.8-LS3.7-BI")
      (description "极性:双向;反向截止电压(Vrwm):6V;钳位电压:10.3V;峰值脉冲电流(Ipp):19.4A;峰值脉冲功率(Ppp):200W;击穿电压(VBR):6.67V;")
      (fields (field (name "Manufacturer") "Liown(里阳半导体)"))
      (libsource (lib "easyedapro") (part "SMF6.0CA_C2990473"))
    )
    (comp (ref "U6")
      (value "2.4GHz")
      (footprint "easyedapro:WIFIM-SMD_ESP-12F-ESP8266MOD")
      (description "核心芯片:ESP8266芯片;频率:2.4GHz;天线形式:板载PCB天线;发射功率:16dBm;接收灵敏度:-90dBm;")
      (fields
        (field (name "Manufacturer Part") "ESP-12F(ESP8266MOD)")
        (field (name "Manufacturer") "Ai-Thinker(安信可)")
      )
      (libsource (lib "easyedapro") (part "ESP-12F(ESP8266MOD)"))
    )
    (comp (ref "U7")
      (value "AHT20")
      (footprint "easyedapro:SENSOR-SMD_L3.0-W3.0-P1.00-BR")
      (description "温度范围:-40°C~+120°C;湿度范围:0%RH~100%RH;接口类型:I2C;湿度精度:±2%RH;")
      (fields (field (name "Manufacturer") "广州奥松"))
      (libsource (lib "easyedapro") (part "AHT20_C2757850"))
    )
    (comp (ref "U8")
      (value "AT24C02")
      (footprint "easyedapro:SOP-8_L5.0-W4.0-P1.27-LS6.0-BL")
      (description "接口类型:I2C;存储容量:2Kbit;时钟频率(fc):1MHz;")
      (fields (field (name "Manufacturer") "IDCHIP(英锐芯)"))
      (libsource (lib "easyedapro") (part "AT24C02"))
    )
    (comp (ref "U9")
      (value "O12864A-GLB-TW3")
      (footprint "easyedapro:LCD-SMD_O12864A-GLB-TW3")
      (description "核心芯片:SSD1306芯片;接口类型:I2C；SPI;尺寸(inch):0.96;像素分辨率:128x64;")
      (fields (field (name "Manufacturer") "Focus Display Solutions Inc."))
      (libsource (lib "easyedapro") (part "O12864A-GLB-TW3"))
    )
    (comp (ref "U10")
      (value "CH340G")
      (footprint "easyedapro:SOIC-16_L9.9-W3.9-P1.27-LS6.0-BL")
      (description "应用功能:USB转UART;USB协议版本:USB 2.0;数据速率:2Mbps;")
      (fields (field (name "Manufacturer") "WCH(南京沁恒)"))
      (libsource (lib "easyedapro") (part "CH340G"))
    )
    (comp (ref "U11")
      (value "AMS1117-3.3")
      (footprint "easyedapro:SOT-223-3_L6.5-W3.4-P2.30-LS7.0-BR")
      (description "输出极性:正极;工作电压:15V;输出电压:3.3V;输出电流:1A;电源纹波抑制比(PSRR):72dB@(120Hz);输出类型:固定;")
      (fields (field (name "Manufacturer") "Advanced Monolithic Systems"))
      (libsource (lib "easyedapro") (part "AMS1117-3.3"))
    )
    (comp (ref "U12")
      (value "INA226AIDGSR")
      (footprint "easyedapro:MSOP-10_L3.0-W3.0-P0.50-LS5.0-BL")
      (description "放大器数:-;共模电压:0V~36V;增益:-;带宽(-3db):-;")
      (fields (field (name "Manufacturer") "TI(德州仪器)"))
      (libsource (lib "easyedapro") (part "INA226AIDGSR"))
    )
    (comp (ref "U13")
      (value "W25Q32JVSSIQ")
      (footprint "easyedapro:SOIC-8_L5.3-W5.3-P1.27-LS8.0-BL")
      (description "接口类型:SPI;存储容量:32Mbit;时钟频率(fc):133MHz;")
      (fields (field (name "Manufacturer") "Winbond(华邦)"))
      (libsource (lib "easyedapro") (part "W25Q32JVSSIQ_C179173"))
    )
    (comp (ref "U14")
      (value "ML621-TZ1")
      (footprint "easyedapro:BAT-SMD_ML621-TZ1")
      (fields (field (name "Manufacturer") "FDK"))
      (libsource (lib "easyedapro") (part "ML621-TZ1"))
    )
    (comp (ref "USB1")
      (value "TYPE-C 16PIN 2MD(073)")
      (footprint "easyedapro:USB-C-SMD_TYPE-C-16PIN-2MD-073")
      (description "连接器类型:Type-C;协议标准:-;公母:母;安装方式:卧贴;触点数量:16P;端口数量:1;额定电流 - 电源:3A;工作温度:-25°C~+85°C;")
      (fields (field (name "Manufacturer") "SHOU HAN(首韩)"))
      (libsource (lib "easyedapro") (part "TYPE-C 16PIN 2MD(073)"))
    )
    (comp (ref "X1")
      (value "12MHz")
      (footprint "easyedapro:CRYSTAL-SMD_4P-L3.2-W2.5-BL")
      (description "晶振类型:贴片晶振;频率:12MHz;常温频差:±10ppm;负载电容:10pF;频率稳定度:±10ppm;")
      (fields
        (field (name "Manufacturer Part") "XC32M4-12.000-F10NNFT")
        (field (name "Manufacturer") "HCI(杭晶)")
      )
      (libsource (lib "easyedapro") (part "XC32M4-12.000-F10NNFT"))
    )
    (comp (ref "X2")
      (value "32.768kHz")
      (footprint "easyedapro:OSC-SMD_L3.2-W1.5")
      (description "晶振类型:贴片晶振;频率:32.768kHz;常温频差:±20ppm;负载电容:12.5pF;频率稳定度:-;")
      (fields (field (name "Manufacturer Part") "SF32WK32768D31T002") (field (name "Manufacturer") "TKD(泰晶)"))
      (libsource (lib "easyedapro") (part "SF32K32768D31T-12.5"))
    )
    (comp (ref "X3")
      (value "8MHz")
      (footprint "easyedapro:CRYSTAL-SMD_L5.0-W3.2")
      (description "晶振类型:贴片晶振;频率:8MHz;常温频差:±10ppm;负载电容:12pF;频率稳定度:±30ppm;")
      (fields
        (field (name "Manufacturer Part") "XC53G2-8.000-F12NJHP")
        (field (name "Manufacturer") "HCI(杭晶)")
      )
      (libsource (lib "easyedapro") (part "XC53G2-8.000-F12NJHP"))
    )
  )
  (nets
    (net (code "1") (name "/ADC_VR") (class "Default")
      (node (ref "R19") (pin "2") (pinfunction "2_2") (pintype "unspecified"))
      (node (ref "U2") (pin "11") (pinfunction "PA1_11") (pintype "unspecified"))
    )
    (net (code "2") (name "/BEEP") (class "Default")
      (node (ref "R21") (pin "2") (pinfunction "2_2") (pintype "input"))
      (node (ref "U2") (pin "2") (pinfunction "PC13-TAMPER-RTC_2") (pintype "unspecified"))
    )
    (net (code "3") (name "/BOOT") (class "Default")
      (node (ref "H2") (pin "1") (pinfunction "1_1") (pintype "unspecified"))
      (node (ref "K1_ISP") (pin "1") (pinfunction "1_1") (pintype "input"))
      (node (ref "R6") (pin "2") (pinfunction "2_2") (pintype "input"))
      (node (ref "U6") (pin "12") (pinfunction "GPIO0_12") (pintype "unspecified"))
    )
    (net (code "4") (name "/BOOT0") (class "Default")
      (node (ref "R25") (pin "2") (pinfunction "2_2") (pintype "input"))
      (node (ref "SW5") (pin "2") (pinfunction "2_2") (pintype "input"))
      (node (ref "U2") (pin "44") (pinfunction "BOOT0_44") (pintype "unspecified"))
    )
    (net (code "5") (name "/CANRX") (class "Default")
      (node (ref "U1") (pin "4") (pinfunction "RXD_4") (pintype "unspecified"))
      (node (ref "U2") (pin "32") (pinfunction "PA11_32") (pintype "unspecified"))
    )
    (net (code "6") (name "/CANTX") (class "Default")
      (node (ref "U1") (pin "1") (pinfunction "TXD_1") (pintype "unspecified"))
      (node (ref "U2") (pin "33") (pinfunction "PA12_33") (pintype "unspecified"))
    )
    (net (code "7") (name "/CS1") (class "Default")
      (node (ref "H8") (pin "12") (pinfunction "12_12") (pintype "unspecified"))
      (node (ref "U2") (pin "10") (pinfunction "PA0-WKUP_10") (pintype "unspecified"))
    )
    (net (code "8") (name "/D+") (class "Default")
      (node (ref "D1") (pin "3") (pinfunction "3_3") (pintype "input"))
      (node (ref "D1") (pin "4") (pinfunction "4_4") (pintype "input"))
      (node (ref "USB1") (pin "A7") (pinfunction "Dn1_A7") (pintype "unspecified"))
      (node (ref "USB1") (pin "B7") (pinfunction "Dn2_B7") (pintype "unspecified"))
    )
    (net (code "9") (name "/D-") (class "Default")
      (node (ref "D1") (pin "1") (pinfunction "1_1") (pintype "input"))
      (node (ref "D1") (pin "6") (pinfunction "6_6") (pintype "input"))
      (node (ref "USB1") (pin "A6") (pinfunction "Dp1_A6") (pintype "unspecified"))
      (node (ref "USB1") (pin "B6") (pinfunction "Dp2_B6") (pintype "unspecified"))
    )
    (net (code "10") (name "/FLASH_CS") (class "Default")
      (node (ref "H8") (pin "21") (pinfunction "21_21") (pintype "unspecified"))
      (node (ref "U13") (pin "1") (pinfunction "CS#_1") (pintype "unspecified"))
      (node (ref "U2") (pin "14") (pinfunction "PA4_14") (pintype "unspecified"))
    )
    (net (code "11") (name "/IN8") (class "Default")
      (node (ref "H8") (pin "7") (pinfunction "7_7") (pintype "unspecified"))
      (node (ref "U2") (pin "18") (pinfunction "PB0_18") (pintype "unspecified"))
    )
    (net (code "12") (name "/JNTRST") (class "Default")
      (node (ref "CN1") (pin "3") (pinfunction "3_3") (pintype "unspecified"))
      (node (ref "U2") (pin "40") (pinfunction "PB4_40") (pintype "unspecified"))
    )
    (net (code "13") (name "/JTCK") (class "Default")
      (node (ref "CN1") (pin "9") (pinfunction "9_9") (pintype "unspecified"))
      (node (ref "R23") (pin "2") (pinfunction "2_2") (pintype "input"))
      (node (ref "U2") (pin "37") (pinfunction "PA14_37") (pintype "unspecified"))
    )
    (net (code "14") (name "/JTDI") (class "Default")
      (node (ref "CN1") (pin "5") (pinfunction "5_5") (pintype "unspecified"))
      (node (ref "U2") (pin "38") (pinfunction "PA15_38") (pintype "unspecified"))
    )
    (net (code "15") (name "/JTDO") (class "Default")
      (node (ref "CN1") (pin "13") (pinfunction "13_13") (pintype "unspecified"))
      (node (ref "U2") (pin "39") (pinfunction "PB3_39") (pintype "unspecified"))
    )
    (net (code "16") (name "/JTMS") (class "Default")
      (node (ref "CN1") (pin "7") (pinfunction "7_7") (pintype "unspecified"))
      (node (ref "R22") (pin "1") (pinfunction "1_1") (pintype "input"))
      (node (ref "U2") (pin "34") (pinfunction "PA13_34") (pintype "unspecified"))
    )
    (net (code "17") (name "/LED1") (class "Default")
      (node (ref "H8") (pin "20") (pinfunction "20_20") (pintype "unspecified"))
      (node (ref "R30") (pin "2") (pinfunction "2_2") (pintype "unspecified"))
      (node (ref "U2") (pin "46") (pinfunction "PB9_46") (pintype "unspecified"))
    )
    (net (code "18") (name "/LED2") (class "Default")
      (node (ref "H8") (pin "22") (pinfunction "22_22") (pintype "unspecified"))
      (node (ref "R31") (pin "2") (pinfunction "2_2") (pintype "unspecified"))
      (node (ref "U2") (pin "45") (pinfunction "PB8_45") (pintype "unspecified"))
    )
    (net (code "19") (name "/MISO1") (class "Default")
      (node (ref "H8") (pin "16") (pinfunction "16_16") (pintype "unspecified"))
      (node (ref "U13") (pin "2") (pinfunction "DO(IO1)_2") (pintype "unspecified"))
      (node (ref "U2") (pin "16") (pinfunction "PA6_16") (pintype "unspecified"))
    )
    (net (code "20") (name "/MOSI1") (class "Default")
      (node (ref "H8") (pin "18") (pinfunction "18_18") (pintype "unspecified"))
      (node (ref "U13") (pin "5") (pinfunction "DI(IO0)_5") (pintype "unspecified"))
      (node (ref "U2") (pin "17") (pinfunction "PA7_17") (pintype "unspecified"))
    )
    (net (code "21") (name "/NRST") (class "Default")
      (node (ref "C32") (pin "1") (pinfunction "1_1") (pintype "unspecified"))
      (node (ref "K5") (pin "1") (pinfunction "1_1") (pintype "unspecified"))
      (node (ref "R18") (pin "2") (pinfunction "2_2") (pintype "input"))
    )
    (net (code "22") (name "/NRTS") (class "Default")
      (node (ref "CN1") (pin "15") (pinfunction "15_15") (pintype "unspecified"))
      (node (ref "U2") (pin "7") (pinfunction "NRST_7") (pintype "unspecified"))
      (node (ref "U6") (pin "1") (pinfunction "RST_1") (pintype "unspecified"))
    )
    (net (code "23") (name "/OSC32_IN") (class "Default")
      (node (ref "C30") (pin "1") (pinfunction "1_1") (pintype "input"))
      (node (ref "R17") (pin "2") (pinfunction "2_2") (pintype "input"))
      (node (ref "U2") (pin "3") (pinfunction "PC14-OSC32IN_3") (pintype "unspecified"))
      (node (ref "X2") (pin "2") (pinfunction "OSC2_2") (pintype "input"))
    )
    (net (code "24") (name "/OSC32_OUT") (class "Default")
      (node (ref "C31") (pin "1") (pinfunction "1_1") (pintype "input"))
      (node (ref "R17") (pin "1") (pinfunction "1_1") (pintype "input"))
      (node (ref "U2") (pin "4") (pinfunction "PC15-OSC32OUT_4") (pintype "unspecified"))
      (node (ref "X2") (pin "1") (pinfunction "OSC1_1") (pintype "input"))
    )
    (net (code "25") (name "/OSC_IN") (class "Default")
      (node (ref "C29") (pin "1") (pinfunction "1_1") (pintype "input"))
      (node (ref "U2") (pin "5") (pinfunction "PD0-OSCIN_5") (pintype "unspecified"))
      (node (ref "X3") (pin "1") (pinfunction "1_1") (pintype "input"))
    )
    (net (code "26") (name "/OSC_OUT") (class "Default")
      (node (ref "C28") (pin "1") (pinfunction "1_1") (pintype "input"))
      (node (ref "U2") (pin "6") (pinfunction "PD1-OSCOUT_6") (pintype "unspecified"))
      (node (ref "X3") (pin "2") (pinfunction "GND_2") (pintype "input"))
    )
    (net (code "27") (name "/RELAY") (class "Default")
      (node (ref "R29") (pin "2") (pinfunction "2_2") (pintype "unspecified"))
      (node (ref "U2") (pin "19") (pinfunction "PB1_19") (pintype "unspecified"))
    )
    (net (code "28") (name "/RS483WR") (class "Default")
      (node (ref "U2") (pin "20") (pinfunction "PB2_20") (pintype "unspecified"))
    )
    (net (code "29") (name "/RS485WR") (class "Default")
      (node (ref "R24") (pin "2") (pinfunction "2_2") (pintype "input"))
      (node (ref "U3") (pin "2") (pinfunction "RE#_2") (pintype "unspecified"))
      (node (ref "U3") (pin "3") (pinfunction "DE_3") (pintype "unspecified"))
    )
    (net (code "30") (name "/RXD1") (class "Default")
      (node (ref "H7") (pin "4") (pinfunction "4_4") (pintype "unspecified"))
      (node (ref "U10") (pin "2") (pinfunction "TXD_2") (pintype "unspecified"))
      (node (ref "U2") (pin "31") (pinfunction "PA10_31") (pintype "unspecified"))
    )
    (net (code "31") (name "/RXD2") (class "Default")
      (node (ref "H6") (pin "4") (pinfunction "4_4") (pintype "unspecified"))
      (node (ref "U2") (pin "13") (pinfunction "PA3_13") (pintype "unspecified"))
      (node (ref "U3") (pin "1") (pinfunction "RO_1") (pintype "unspecified"))
    )
    (net (code "32") (name "/RXD3") (class "Default")
      (node (ref "SW1") (pin "5") (pinfunction "5_5") (pintype "unspecified"))
      (node (ref "U2") (pin "22") (pinfunction "PB11_22") (pintype "unspecified"))
    )
    (net (code "33") (name "/RXD3_4G") (class "Default")
      (node (ref "H1") (pin "4") (pinfunction "4_4") (pintype "unspecified"))
      (node (ref "H3") (pin "4") (pinfunction "4_4") (pintype "unspecified"))
      (node (ref "SW1") (pin "6") (pinfunction "6_6") (pintype "unspecified"))
    )
    (net (code "34") (name "/RXD3_WIFI") (class "Default")
      (node (ref "SW1") (pin "4") (pinfunction "4_4") (pintype "unspecified"))
      (node (ref "U6") (pin "16") (pinfunction "TXD0_16") (pintype "unspecified"))
    )
    (net (code "35") (name "/SCL1") (class "Default")
      (node (ref "H8") (pin "10") (pinfunction "10_10") (pintype "unspecified"))
      (node (ref "R9") (pin "1") (pinfunction "1_1") (pintype "input"))
      (node (ref "U12") (pin "5") (pinfunction "SCL_5") (pintype "unspecified"))
      (node (ref "U2") (pin "42") (pinfunction "PB6_42") (pintype "unspecified"))
      (node (ref "U7") (pin "3") (pinfunction "SCL_3") (pintype "unspecified"))
      (node (ref "U8") (pin "6") (pinfunction "SCL_6") (pintype "unspecified"))
      (node (ref "U9") (pin "18") (pinfunction "D0_18") (pintype "unspecified"))
    )
    (net (code "36") (name "/SCLK1") (class "Default")
      (node (ref "H8") (pin "14") (pinfunction "14_14") (pintype "unspecified"))
      (node (ref "U13") (pin "6") (pinfunction "CLK_6") (pintype "unspecified"))
      (node (ref "U2") (pin "15") (pinfunction "PA5_15") (pintype "unspecified"))
    )
    (net (code "37") (name "/SDA1") (class "Default")
      (node (ref "H8") (pin "8") (pinfunction "8_8") (pintype "unspecified"))
      (node (ref "R10") (pin "1") (pinfunction "1_1") (pintype "input"))
      (node (ref "U12") (pin "4") (pinfunction "SDA_4") (pintype "unspecified"))
      (node (ref "U2") (pin "43") (pinfunction "PB7_43") (pintype "unspecified"))
      (node (ref "U7") (pin "4") (pinfunction "SDA_4") (pintype "unspecified"))
      (node (ref "U8") (pin "5") (pinfunction "SDA_5") (pintype "unspecified"))
      (node (ref "U9") (pin "19") (pinfunction "D1_19") (pintype "unspecified"))
      (node (ref "U9") (pin "20") (pinfunction "D2_20") (pintype "unspecified"))
    )
    (net (code "38") (name "/SE_OK") (class "Default")
      (node (ref "H8") (pin "13") (pinfunction "13_13") (pintype "unspecified"))
    )
    (net (code "39") (name "/SW_DOWN") (class "Default")
      (node (ref "H8") (pin "15") (pinfunction "15_15") (pintype "unspecified"))
      (node (ref "K6") (pin "1") (pinfunction "1_1") (pintype "unspecified"))
      (node (ref "R33") (pin "1") (pinfunction "1_1") (pintype "input"))
      (node (ref "U2") (pin "27") (pinfunction "PB14_27") (pintype "unspecified"))
    )
    (net (code "40") (name "/SW_ESC") (class "Default")
      (node (ref "H8") (pin "11") (pinfunction "11_11") (pintype "unspecified"))
      (node (ref "K7") (pin "2") (pinfunction "2_2") (pintype "unspecified"))
      (node (ref "R36") (pin "1") (pinfunction "1_1") (pintype "input"))
      (node (ref "U2") (pin "29") (pinfunction "PA8_29") (pintype "unspecified"))
    )
    (net (code "41") (name "/SW_LEFT") (class "Default")
      (node (ref "H8") (pin "9") (pinfunction "9_9") (pintype "unspecified"))
      (node (ref "K3") (pin "1") (pinfunction "1_1") (pintype "unspecified"))
      (node (ref "R32") (pin "1") (pinfunction "1_1") (pintype "input"))
      (node (ref "U2") (pin "41") (pinfunction "PB5_41") (pintype "unspecified"))
    )
    (net (code "42") (name "/SW_OK") (class "Default")
      (node (ref "K8") (pin "1") (pinfunction "1_1") (pintype "unspecified"))
      (node (ref "R37") (pin "1") (pinfunction "1_1") (pintype "input"))
      (node (ref "U2") (pin "25") (pinfunction "PB12_25") (pintype "unspecified"))
    )
    (net (code "43") (name "/SW_RIGHT") (class "Default")
      (node (ref "H8") (pin "19") (pinfunction "19_19") (pintype "unspecified"))
      (node (ref "K4") (pin "2") (pinfunction "2_2") (pintype "unspecified"))
      (node (ref "R34") (pin "1") (pinfunction "1_1") (pintype "input"))
      (node (ref "U2") (pin "28") (pinfunction "PB15_28") (pintype "unspecified"))
    )
    (net (code "44") (name "/SW_UP") (class "Default")
      (node (ref "H8") (pin "17") (pinfunction "17_17") (pintype "unspecified"))
      (node (ref "K2") (pin "2") (pinfunction "2_2") (pintype "unspecified"))
      (node (ref "R35") (pin "1") (pinfunction "1_1") (pintype "input"))
      (node (ref "U2") (pin "26") (pinfunction "PB13_26") (pintype "unspecified"))
    )
    (net (code "45") (name "/TXD1") (class "Default")
      (node (ref "H7") (pin "3") (pinfunction "3_3") (pintype "unspecified"))
      (node (ref "U10") (pin "3") (pinfunction "RXD_3") (pintype "unspecified"))
      (node (ref "U2") (pin "30") (pinfunction "PA9_30") (pintype "unspecified"))
    )
    (net (code "46") (name "/TXD2") (class "Default")
      (node (ref "H6") (pin "3") (pinfunction "3_3") (pintype "unspecified"))
      (node (ref "U2") (pin "12") (pinfunction "PA2_12") (pintype "unspecified"))
      (node (ref "U3") (pin "4") (pinfunction "DI_4") (pintype "unspecified"))
    )
    (net (code "47") (name "/TXD3") (class "Default")
      (node (ref "SW1") (pin "2") (pinfunction "2_2") (pintype "unspecified"))
      (node (ref "U2") (pin "21") (pinfunction "PB10_21") (pintype "unspecified"))
    )
    (net (code "48") (name "/TXD3_4G") (class "Default")
      (node (ref "H1") (pin "3") (pinfunction "3_3") (pintype "unspecified"))
      (node (ref "H3") (pin "3") (pinfunction "3_3") (pintype "unspecified"))
      (node (ref "SW1") (pin "3") (pinfunction "3_3") (pintype "unspecified"))
    )
    (net (code "49") (name "/TXD3_WIFI") (class "Default")
      (node (ref "SW1") (pin "1") (pinfunction "1_1") (pintype "unspecified"))
      (node (ref "U6") (pin "15") (pinfunction "RXD0_15") (pintype "unspecified"))
    )
    (net (code "50") (name "GND") (class "Default")
      (node (ref "C1") (pin "2") (pinfunction "2_2") (pintype "input"))
      (node (ref "C13") (pin "1") (pinfunction "1_1") (pintype "unspecified"))
      (node (ref "C14") (pin "1") (pinfunction "1_1") (pintype "unspecified"))
      (node (ref "C15") (pin "1") (pinfunction "1_1") (pintype "unspecified"))
      (node (ref "C16") (pin "2") (pinfunction "2_2") (pintype "unspecified"))
      (node (ref "C17") (pin "2") (pinfunction "2_2") (pintype "unspecified"))
      (node (ref "C18") (pin "2") (pinfunction "2_2") (pintype "unspecified"))
      (node (ref "C19") (pin "2") (pinfunction "2_2") (pintype "unspecified"))
      (node (ref "C2") (pin "2") (pinfunction "2_2") (pintype "input"))
      (node (ref "C20") (pin "2") (pinfunction "2_2") (pintype "unspecified"))
      (node (ref "C21") (pin "2") (pinfunction "2_2") (pintype "input"))
      (node (ref "C22") (pin "2") (pinfunction "2_2") (pintype "input"))
      (node (ref "C23") (pin "2") (pinfunction "2_2") (pintype "unspecified"))
      (node (ref "C24") (pin "1") (pinfunction "1_1") (pintype "input"))
      (node (ref "C25") (pin "1") (pinfunction "1_1") (pintype "unspecified"))
      (node (ref "C26") (pin "1") (pinfunction "1_1") (pintype "unspecified"))
      (node (ref "C27") (pin "2") (pinfunction "2_2") (pintype "unspecified"))
      (node (ref "C28") (pin "2") (pinfunction "2_2") (pintype "input"))
      (node (ref "C29") (pin "2") (pinfunction "2_2") (pintype "input"))
      (node (ref "C3") (pin "2") (pinfunction "2_2") (pintype "input"))
      (node (ref "C30") (pin "2") (pinfunction "2_2") (pintype "input"))
      (node (ref "C31") (pin "2") (pinfunction "2_2") (pintype "input"))
      (node (ref "C32") (pin "2") (pinfunction "2_2") (pintype "unspecified"))
      (node (ref "C33") (pin "1") (pinfunction "1_1") (pintype "unspecified"))
      (node (ref "C34") (pin "2") (pinfunction "2_2") (pintype "unspecified"))
      (node (ref "C35") (pin "1") (pinfunction "1_1") (pintype "unspecified"))
      (node (ref "C4") (pin "1") (pinfunction "1_1") (pintype "input"))
      (node (ref "C5") (pin "2") (pinfunction "2_2") (pintype "unspecified"))
      (node (ref "C6") (pin "1") (pinfunction "1_1") (pintype "unspecified"))
      (node (ref "C7") (pin "1") (pinfunction "1_1") (pintype "unspecified"))
      (node (ref "C8") (pin "1") (pinfunction "1_1") (pintype "unspecified"))
      (node (ref "CN1") (pin "10") (pinfunction "10_10") (pintype "unspecified"))
      (node (ref "CN1") (pin "12") (pinfunction "12_12") (pintype "unspecified"))
      (node (ref "CN1") (pin "14") (pinfunction "14_14") (pintype "unspecified"))
      (node (ref "CN1") (pin "16") (pinfunction "16_16") (pintype "unspecified"))
      (node (ref "CN1") (pin "18") (pinfunction "18_18") (pintype "unspecified"))
      (node (ref "CN1") (pin "20") (pinfunction "20_20") (pintype "unspecified"))
      (node (ref "CN1") (pin "4") (pinfunction "4_4") (pintype "unspecified"))
      (node (ref "CN1") (pin "6") (pinfunction "6_6") (pintype "unspecified"))
      (node (ref "CN1") (pin "8") (pinfunction "8_8") (pintype "unspecified"))
      (node (ref "D1") (pin "2") (pinfunction "2_2") (pintype "input"))
      (node (ref "H1") (pin "5") (pinfunction "5_5") (pintype "unspecified"))
      (node (ref "H2") (pin "5") (pinfunction "5_5") (pintype "unspecified"))
      (node (ref "H3") (pin "2") (pinfunction "2_2") (pintype "unspecified"))
      (node (ref "H4") (pin "2") (pinfunction "2_2") (pintype "unspecified"))
      (node (ref "H5") (pin "2") (pinfunction "2_2") (pintype "unspecified"))
      (node (ref "H6") (pin "2") (pinfunction "2_2") (pintype "unspecified"))
      (node (ref "H7") (pin "2") (pinfunction "2_2") (pintype "unspecified"))
      (node (ref "H8") (pin "1") (pinfunction "1_1") (pintype "unspecified"))
      (node (ref "H8") (pin "2") (pinfunction "2_2") (pintype "unspecified"))
      (node (ref "K1_ISP") (pin "2") (pinfunction "2_2") (pintype "input"))
      (node (ref "K2") (pin "1") (pinfunction "1_1") (pintype "unspecified"))
      (node (ref "K3") (pin "2") (pinfunction "2_2") (pintype "unspecified"))
      (node (ref "K4") (pin "1") (pinfunction "1_1") (pintype "unspecified"))
      (node (ref "K5") (pin "2") (pinfunction "2_2") (pintype "unspecified"))
      (node (ref "K6") (pin "2") (pinfunction "2_2") (pintype "unspecified"))
      (node (ref "K7") (pin "1") (pinfunction "1_1") (pintype "unspecified"))
      (node (ref "K8") (pin "2") (pinfunction "2_2") (pintype "unspecified"))
      (node (ref "LED1") (pin "1") (pinfunction "C_1") (pintype "input"))
      (node (ref "Q1") (pin "2") (pinfunction "E_2") (pintype "input"))
      (node (ref "R12") (pin "2") (pinfunction "2_2") (pintype "input"))
      (node (ref "R13") (pin "1") (pinfunction "1_1") (pintype "input"))
      (node (ref "R14") (pin "1") (pinfunction "1_1") (pintype "input"))
      (node (ref "R19") (pin "1") (pinfunction "1_1") (pintype "unspecified"))
      (node (ref "R23") (pin "1") (pinfunction "1_1") (pintype "input"))
      (node (ref "R24") (pin "1") (pinfunction "1_1") (pintype "input"))
      (node (ref "R25") (pin "1") (pinfunction "1_1") (pintype "input"))
      (node (ref "R3") (pin "2") (pinfunction "2_2") (pintype "input"))
      (node (ref "R8") (pin "1") (pinfunction "1_1") (pintype "input"))
      (node (ref "U1") (pin "2") (pinfunction "GND_2") (pintype "unspecified"))
      (node (ref "U1") (pin "8") (pinfunction "STB_8") (pintype "unspecified"))
      (node (ref "U10") (pin "1") (pinfunction "GND_1") (pintype "unspecified"))
      (node (ref "U11") (pin "1") (pinfunction "GND_1") (pintype "unspecified"))
      (node (ref "U12") (pin "1") (pinfunction "A1_1") (pintype "unspecified"))
      (node (ref "U12") (pin "7") (pinfunction "GND_7") (pintype "unspecified"))
      (node (ref "U13") (pin "4") (pinfunction "GND_4") (pintype "unspecified"))
      (node (ref "U14") (pin "2") (pinfunction "2_2") (pintype "input"))
      (node (ref "U2") (pin "23") (pinfunction "VSS_1_23") (pintype "unspecified"))
      (node (ref "U2") (pin "35") (pinfunction "VSS_2_35") (pintype "unspecified"))
      (node (ref "U2") (pin "47") (pinfunction "VSS_3_47") (pintype "unspecified"))
      (node (ref "U2") (pin "8") (pinfunction "VSSA_8") (pintype "unspecified"))
      (node (ref "U3") (pin "5") (pinfunction "GND_5") (pintype "unspecified"))
      (node (ref "U4") (pin "2") (pinfunction "2_2") (pintype "unspecified"))
      (node (ref "U5") (pin "1") (pinfunction "1_1") (pintype "unspecified"))
      (node (ref "U6") (pin "9") (pinfunction "GND_9") (pintype "unspecified"))
      (node (ref "U7") (pin "5") (pinfunction "GND_5") (pintype "unspecified"))
      (node (ref "U8") (pin "1") (pinfunction "A0_1") (pintype "unspecified"))
      (node (ref "U8") (pin "2") (pinfunction "A1_2") (pintype "unspecified"))
      (node (ref "U8") (pin "3") (pinfunction "A2_3") (pintype "unspecified"))
      (node (ref "U8") (pin "4") (pinfunction "GND_4") (pintype "unspecified"))
      (node (ref "U8") (pin "7") (pinfunction "WP_7") (pintype "unspecified"))
      (node (ref "U9") (pin "1") (pinfunction "N.C.(GND)_1") (pintype "unspecified"))
      (node (ref "U9") (pin "12") (pinfunction "BS2_12") (pintype "unspecified"))
      (node (ref "U9") (pin "13") (pinfunction "CS#_13") (pintype "unspecified"))
      (node (ref "U9") (pin "16") (pinfunction "R/W#_16") (pintype "unspecified"))
      (node (ref "U9") (pin "17") (pinfunction "E/RD#_17") (pintype "unspecified"))
      (node (ref "U9") (pin "21") (pinfunction "D3_21") (pintype "unspecified"))
      (node (ref "U9") (pin "22") (pinfunction "D4_22") (pintype "unspecified"))
      (node (ref "U9") (pin "23") (pinfunction "D5_23") (pintype "unspecified"))
      (node (ref "U9") (pin "24") (pinfunction "D6_24") (pintype "unspecified"))
      (node (ref "U9") (pin "25") (pinfunction "D7_25") (pintype "unspecified"))
      (node (ref "U9") (pin "29") (pinfunction "VLSS_29") (pintype "unspecified"))
      (node (ref "U9") (pin "30") (pinfunction "N.C.(GND)_30") (pintype "unspecified"))
      (node (ref "U9") (pin "8") (pinfunction "VSS_8") (pintype "unspecified"))
      (node (ref "USB1") (pin "A1B12") (pinfunction "GND_A1B12") (pintype "unspecified"))
      (node (ref "USB1") (pin "B1A12") (pinfunction "GND_B1A12") (pintype "unspecified"))
      (node (ref "X1") (pin "2") (pinfunction "GND_2") (pintype "input"))
      (node (ref "X1") (pin "4") (pinfunction "GND_4") (pintype "input"))
    )
    (net (code "51") (name "Net-(C20-Pad1)") (class "Default")
      (node (ref "C20") (pin "1") (pinfunction "1_1") (pintype "unspecified"))
      (node (ref "R14") (pin "2") (pinfunction "2_2") (pintype "input"))
      (node (ref "USB1") (pin "13") (pinfunction "EH_13") (pintype "unspecified"))
      (node (ref "USB1") (pin "14") (pinfunction "EH_14") (pintype "unspecified"))
    )
    (net (code "52") (name "Net-(D2-A)") (class "Default")
      (node (ref "D2") (pin "2") (pinfunction "A_2") (pintype "unspecified"))
      (node (ref "Q2") (pin "3") (pinfunction "C_3") (pintype "input"))
      (node (ref "R26") (pin "1") (pinfunction "1_1") (pintype "unspecified"))
      (node (ref "RELAY1") (pin "1") (pinfunction "1_1") (pintype "input"))
    )
    (net (code "53") (name "Net-(H1-Pad2)") (class "Default")
      (node (ref "H1") (pin "2") (pinfunction "2_2") (pintype "unspecified"))
      (node (ref "R20") (pin "1") (pinfunction "1_1") (pintype "input"))
    )
    (net (code "54") (name "Net-(J1-Pad1)") (class "Default")
      (node (ref "J1") (pin "1") (pinfunction "1_1") (pintype "unspecified"))
      (node (ref "RELAY1") (pin "3") (pinfunction "3_3") (pintype "input"))
    )
    (net (code "55") (name "Net-(J1-Pad2)") (class "Default")
      (node (ref "J1") (pin "2") (pinfunction "2_2") (pintype "unspecified"))
      (node (ref "RELAY1") (pin "5") (pinfunction "5_5") (pintype "input"))
    )
    (net (code "56") (name "Net-(J1-Pad3)") (class "Default")
      (node (ref "J1") (pin "3") (pinfunction "3_3") (pintype "unspecified"))
      (node (ref "RELAY1") (pin "2") (pinfunction "2_2") (pintype "input"))
    )
    (net (code "57") (name "Net-(LED1-A)") (class "Default")
      (node (ref "LED1") (pin "2") (pinfunction "A_2") (pintype "input"))
      (node (ref "R16") (pin "1") (pinfunction "1_1") (pintype "input"))
    )
    (net (code "58") (name "Net-(LED2-C)") (class "Default")
      (node (ref "LED2") (pin "1") (pinfunction "C_1") (pintype "input"))
      (node (ref "R26") (pin "2") (pinfunction "2_2") (pintype "unspecified"))
    )
    (net (code "59") (name "Net-(LED3-A)") (class "Default")
      (node (ref "LED3") (pin "2") (pinfunction "A_2") (pintype "input"))
      (node (ref "R30") (pin "1") (pinfunction "1_1") (pintype "unspecified"))
    )
    (net (code "60") (name "Net-(LED4-A)") (class "Default")
      (node (ref "LED4") (pin "2") (pinfunction "A_2") (pintype "input"))
      (node (ref "R31") (pin "1") (pinfunction "1_1") (pintype "unspecified"))
    )
    (net (code "61") (name "Net-(Q1-B)") (class "Default")
      (node (ref "Q1") (pin "1") (pinfunction "B_1") (pintype "input"))
      (node (ref "R21") (pin "1") (pinfunction "1_1") (pintype "input"))
    )
    (net (code "62") (name "Net-(Q1-C)") (class "Default")
      (node (ref "BUZZER1") (pin "2") (pinfunction "2_2") (pintype "unspecified"))
      (node (ref "Q1") (pin "3") (pinfunction "C_3") (pintype "input"))
    )
    (net (code "63") (name "Net-(Q2-B)") (class "Default")
      (node (ref "Q2") (pin "1") (pinfunction "B_1") (pintype "input"))
      (node (ref "R27") (pin "2") (pinfunction "2_2") (pintype "input"))
      (node (ref "R28") (pin "1") (pinfunction "1_1") (pintype "unspecified"))
    )
    (net (code "64") (name "Net-(Q2-E)") (class "Default")
      (node (ref "Q2") (pin "2") (pinfunction "E_2") (pintype "input"))
      (node (ref "R27") (pin "1") (pinfunction "1_1") (pintype "input"))
    )
    (net (code "65") (name "Net-(Q3-B)") (class "Default")
      (node (ref "Q3") (pin "1") (pinfunction "B_1") (pintype "input"))
      (node (ref "R29") (pin "1") (pinfunction "1_1") (pintype "unspecified"))
    )
    (net (code "66") (name "Net-(Q3-E)") (class "Default")
      (node (ref "Q3") (pin "2") (pinfunction "E_2") (pintype "input"))
      (node (ref "R28") (pin "2") (pinfunction "2_2") (pintype "unspecified"))
    )
    (net (code "67") (name "Net-(SW3-Pad1)") (class "Default")
      (node (ref "SW3") (pin "1") (pinfunction "1_1") (pintype "unspecified"))
      (node (ref "SW3") (pin "4") (pinfunction "4_4") (pintype "unspecified"))
    )
    (net (code "68") (name "Net-(U1-CANH)") (class "Default")
      (node (ref "C3") (pin "1") (pinfunction "1_1") (pintype "input"))
      (node (ref "H4") (pin "3") (pinfunction "3_3") (pintype "unspecified"))
      (node (ref "R2") (pin "2") (pinfunction "2_2") (pintype "input"))
      (node (ref "U1") (pin "7") (pinfunction "CANH_7") (pintype "unspecified"))
    )
    (net (code "69") (name "Net-(U1-CANL)") (class "Default")
      (node (ref "C4") (pin "2") (pinfunction "2_2") (pintype "input"))
      (node (ref "H4") (pin "4") (pinfunction "4_4") (pintype "unspecified"))
      (node (ref "R2") (pin "1") (pinfunction "1_1") (pintype "input"))
      (node (ref "U1") (pin "6") (pinfunction "CANL_6") (pintype "unspecified"))
    )
    (net (code "70") (name "Net-(U2-VBAT)") (class "Default")
      (node (ref "U14") (pin "1") (pinfunction "1_1") (pintype "input"))
      (node (ref "U2") (pin "1") (pinfunction "VBAT_1") (pintype "unspecified"))
    )
    (net (code "71") (name "Net-(U3-A)") (class "Default")
      (node (ref "H5") (pin "4") (pinfunction "4_4") (pintype "unspecified"))
      (node (ref "R4") (pin "2") (pinfunction "2_2") (pintype "input"))
      (node (ref "R5") (pin "1") (pinfunction "1_1") (pintype "unspecified"))
      (node (ref "U3") (pin "6") (pinfunction "A_6") (pintype "unspecified"))
      (node (ref "U5") (pin "2") (pinfunction "2_2") (pintype "unspecified"))
    )
    (net (code "72") (name "Net-(U3-B)") (class "Default")
      (node (ref "H5") (pin "3") (pinfunction "3_3") (pintype "unspecified"))
      (node (ref "R3") (pin "1") (pinfunction "1_1") (pintype "input"))
      (node (ref "R5") (pin "2") (pinfunction "2_2") (pintype "unspecified"))
      (node (ref "U3") (pin "7") (pinfunction "B_7") (pintype "unspecified"))
      (node (ref "U4") (pin "1") (pinfunction "1_1") (pintype "unspecified"))
    )
    (net (code "73") (name "Net-(U6-EN)") (class "Default")
      (node (ref "R7") (pin "1") (pinfunction "1_1") (pintype "input"))
      (node (ref "U6") (pin "3") (pinfunction "EN_3") (pintype "unspecified"))
    )
    (net (code "74") (name "Net-(U6-GPIO15)") (class "Default")
      (node (ref "R8") (pin "2") (pinfunction "2_2") (pintype "input"))
      (node (ref "U6") (pin "10") (pinfunction "GPIO15_10") (pintype "unspecified"))
    )
    (net (code "75") (name "Net-(U8-VCC)") (class "Default")
      (node (ref "C8") (pin "2") (pinfunction "2_2") (pintype "unspecified"))
      (node (ref "U8") (pin "8") (pinfunction "VCC_8") (pintype "unspecified"))
    )
    (net (code "76") (name "Net-(U9-BS0)") (class "Default")
      (node (ref "C11") (pin "1") (pinfunction "1_1") (pintype "input"))
      (node (ref "C12") (pin "1") (pinfunction "1_1") (pintype "input"))
      (node (ref "U9") (pin "10") (pinfunction "BS0_10") (pintype "unspecified"))
    )
    (net (code "77") (name "Net-(U9-C1N)") (class "Default")
      (node (ref "C10") (pin "1") (pinfunction "1_1") (pintype "input"))
      (node (ref "U9") (pin "5") (pinfunction "C1N_5") (pintype "unspecified"))
    )
    (net (code "78") (name "Net-(U9-C1P)") (class "Default")
      (node (ref "C10") (pin "2") (pinfunction "2_2") (pintype "input"))
      (node (ref "U9") (pin "4") (pinfunction "C1P_4") (pintype "unspecified"))
    )
    (net (code "79") (name "Net-(U9-C2N)") (class "Default")
      (node (ref "C9") (pin "1") (pinfunction "1_1") (pintype "input"))
      (node (ref "U9") (pin "3") (pinfunction "C2N_3") (pintype "unspecified"))
    )
    (net (code "80") (name "Net-(U9-C2P)") (class "Default")
      (node (ref "C9") (pin "2") (pinfunction "2_2") (pintype "input"))
      (node (ref "U9") (pin "2") (pinfunction "C2P_2") (pintype "unspecified"))
    )
    (net (code "81") (name "Net-(U9-D{slash}C#)") (class "Default")
      (node (ref "R12") (pin "1") (pinfunction "1_1") (pintype "input"))
      (node (ref "U9") (pin "15") (pinfunction "D/C#_15") (pintype "unspecified"))
    )
    (net (code "82") (name "Net-(U9-IREF)") (class "Default")
      (node (ref "R13") (pin "2") (pinfunction "2_2") (pintype "input"))
      (node (ref "U9") (pin "26") (pinfunction "IREF_26") (pintype "unspecified"))
    )
    (net (code "83") (name "Net-(U9-RES#)") (class "Default")
      (node (ref "C13") (pin "2") (pinfunction "2_2") (pintype "unspecified"))
      (node (ref "R11") (pin "1") (pinfunction "1_1") (pintype "input"))
      (node (ref "U9") (pin "14") (pinfunction "RES#_14") (pintype "unspecified"))
    )
    (net (code "84") (name "Net-(U9-VCC)") (class "Default")
      (node (ref "C15") (pin "2") (pinfunction "2_2") (pintype "unspecified"))
      (node (ref "U9") (pin "28") (pinfunction "VCC_28") (pintype "unspecified"))
    )
    (net (code "85") (name "Net-(U9-VCOMH)") (class "Default")
      (node (ref "C14") (pin "2") (pinfunction "2_2") (pintype "unspecified"))
      (node (ref "U9") (pin "27") (pinfunction "VCOMH_27") (pintype "unspecified"))
    )
    (net (code "86") (name "Net-(U10-V3)") (class "Default")
      (node (ref "C17") (pin "1") (pinfunction "1_1") (pintype "unspecified"))
      (node (ref "U10") (pin "4") (pinfunction "V3_4") (pintype "unspecified"))
    )
    (net (code "87") (name "Net-(U10-XI)") (class "Default")
      (node (ref "C18") (pin "1") (pinfunction "1_1") (pintype "unspecified"))
      (node (ref "U10") (pin "7") (pinfunction "XI_7") (pintype "unspecified"))
    )
    (net (code "88") (name "Net-(U10-XO)") (class "Default")
      (node (ref "C19") (pin "1") (pinfunction "1_1") (pintype "unspecified"))
      (node (ref "U10") (pin "8") (pinfunction "XO_8") (pintype "unspecified"))
      (node (ref "X1") (pin "3") (pinfunction "3_3") (pintype "input"))
    )
    (net (code "89") (name "VCC3V3") (class "Default")
      (node (ref "BUZZER1") (pin "1") (pinfunction "+_1") (pintype "unspecified"))
      (node (ref "C11") (pin "2") (pinfunction "2_2") (pintype "input"))
      (node (ref "C12") (pin "2") (pinfunction "2_2") (pintype "input"))
      (node (ref "C26") (pin "2") (pinfunction "2_2") (pintype "unspecified"))
      (node (ref "C27") (pin "1") (pinfunction "1_1") (pintype "unspecified"))
      (node (ref "C33") (pin "2") (pinfunction "2_2") (pintype "unspecified"))
      (node (ref "C34") (pin "1") (pinfunction "1_1") (pintype "unspecified"))
      (node (ref "C35") (pin "2") (pinfunction "2_2") (pintype "unspecified"))
      (node (ref "C5") (pin "1") (pinfunction "1_1") (pintype "unspecified"))
      (node (ref "C6") (pin "2") (pinfunction "2_2") (pintype "unspecified"))
      (node (ref "C7") (pin "2") (pinfunction "2_2") (pintype "unspecified"))
      (node (ref "CN1") (pin "1") (pinfunction "1_1") (pintype "unspecified"))
      (node (ref "CN1") (pin "2") (pinfunction "2_2") (pintype "unspecified"))
      (node (ref "H3") (pin "1") (pinfunction "1_1") (pintype "unspecified"))
      (node (ref "H6") (pin "1") (pinfunction "1_1") (pintype "unspecified"))
      (node (ref "H7") (pin "1") (pinfunction "1_1") (pintype "unspecified"))
      (node (ref "H8") (pin "3") (pinfunction "3_3") (pintype "unspecified"))
      (node (ref "H8") (pin "4") (pinfunction "4_4") (pintype "unspecified"))
      (node (ref "LED3") (pin "1") (pinfunction "C_1") (pintype "input"))
      (node (ref "LED4") (pin "1") (pinfunction "C_1") (pintype "input"))
      (node (ref "R10") (pin "2") (pinfunction "2_2") (pintype "input"))
      (node (ref "R11") (pin "2") (pinfunction "2_2") (pintype "input"))
      (node (ref "R16") (pin "2") (pinfunction "2_2") (pintype "input"))
      (node (ref "R18") (pin "1") (pinfunction "1_1") (pintype "input"))
      (node (ref "R19") (pin "3") (pinfunction "3_3") (pintype "unspecified"))
      (node (ref "R22") (pin "2") (pinfunction "2_2") (pintype "input"))
      (node (ref "R32") (pin "2") (pinfunction "2_2") (pintype "input"))
      (node (ref "R33") (pin "2") (pinfunction "2_2") (pintype "input"))
      (node (ref "R34") (pin "2") (pinfunction "2_2") (pintype "input"))
      (node (ref "R35") (pin "2") (pinfunction "2_2") (pintype "input"))
      (node (ref "R36") (pin "2") (pinfunction "2_2") (pintype "input"))
      (node (ref "R37") (pin "2") (pinfunction "2_2") (pintype "input"))
      (node (ref "R4") (pin "1") (pinfunction "1_1") (pintype "input"))
      (node (ref "R6") (pin "1") (pinfunction "1_1") (pintype "input"))
      (node (ref "R7") (pin "2") (pinfunction "2_2") (pintype "input"))
      (node (ref "R9") (pin "2") (pinfunction "2_2") (pintype "input"))
      (node (ref "SW5") (pin "1") (pinfunction "A1_1") (pintype "input"))
      (node (ref "U11") (pin "4") (pinfunction "VOUT_4") (pintype "unspecified"))
      (node (ref "U12") (pin "2") (pinfunction "A0_2") (pintype "unspecified"))
      (node (ref "U12") (pin "6") (pinfunction "VS+_6") (pintype "unspecified"))
      (node (ref "U13") (pin "3") (pinfunction "WP#(IO2)_3") (pintype "unspecified"))
      (node (ref "U13") (pin "7") (pinfunction "HOLD#_or_RESET#(IO3)_7") (pintype "unspecified"))
      (node (ref "U13") (pin "8") (pinfunction "VCC_8") (pintype "unspecified"))
      (node (ref "U2") (pin "24") (pinfunction "VDD_1_24") (pintype "unspecified"))
      (node (ref "U2") (pin "36") (pinfunction "VDD_2_36") (pintype "unspecified"))
      (node (ref "U2") (pin "48") (pinfunction "VDD_3_48") (pintype "unspecified"))
      (node (ref "U2") (pin "9") (pinfunction "VDDA_9") (pintype "unspecified"))
      (node (ref "U3") (pin "8") (pinfunction "VCC_8") (pintype "unspecified"))
      (node (ref "U6") (pin "8") (pinfunction "VCC_8") (pintype "unspecified"))
      (node (ref "U7") (pin "2") (pinfunction "VDD_2") (pintype "unspecified"))
      (node (ref "U9") (pin "11") (pinfunction "BS1_11") (pintype "unspecified"))
      (node (ref "U9") (pin "6") (pinfunction "VBAT_6") (pintype "unspecified"))
      (node (ref "U9") (pin "9") (pinfunction "VDD_9") (pintype "unspecified"))
    )
    (net (code "90") (name "VCC5V") (class "Default")
      (node (ref "C1") (pin "1") (pinfunction "1_1") (pintype "input"))
      (node (ref "C16") (pin "1") (pinfunction "1_1") (pintype "unspecified"))
      (node (ref "C2") (pin "1") (pinfunction "1_1") (pintype "input"))
      (node (ref "C23") (pin "1") (pinfunction "1_1") (pintype "unspecified"))
      (node (ref "C24") (pin "2") (pinfunction "2_2") (pintype "input"))
      (node (ref "C25") (pin "2") (pinfunction "2_2") (pintype "unspecified"))
      (node (ref "D2") (pin "1") (pinfunction "K_1") (pintype "unspecified"))
      (node (ref "H1") (pin "6") (pinfunction "6_6") (pintype "unspecified"))
      (node (ref "H2") (pin "6") (pinfunction "6_6") (pintype "unspecified"))
      (node (ref "H8") (pin "5") (pinfunction "5_5") (pintype "unspecified"))
      (node (ref "H8") (pin "6") (pinfunction "6_6") (pintype "unspecified"))
      (node (ref "LED2") (pin "2") (pinfunction "A_2") (pintype "input"))
      (node (ref "Q3") (pin "3") (pinfunction "C_3") (pintype "input"))
      (node (ref "R15") (pin "2") (pinfunction "2_2") (pintype "unspecified"))
      (node (ref "R20") (pin "2") (pinfunction "2_2") (pintype "input"))
      (node (ref "RELAY1") (pin "4") (pinfunction "4_4") (pintype "input"))
      (node (ref "U1") (pin "3") (pinfunction "VCC_3") (pintype "unspecified"))
      (node (ref "U10") (pin "16") (pinfunction "VCC_16") (pintype "unspecified"))
      (node (ref "U11") (pin "3") (pinfunction "VIN_3") (pintype "unspecified"))
      (node (ref "U12") (pin "9") (pinfunction "VIN-_9") (pintype "unspecified"))
    )
    (net (code "91") (name "VCCBUS") (class "Default")
      (node (ref "C21") (pin "1") (pinfunction "1_1") (pintype "input"))
      (node (ref "C22") (pin "1") (pinfunction "1_1") (pintype "input"))
      (node (ref "D1") (pin "5") (pinfunction "5_5") (pintype "input"))
      (node (ref "SW3") (pin "3") (pinfunction "3_3") (pintype "unspecified"))
      (node (ref "SW3") (pin "6") (pinfunction "6_6") (pintype "unspecified"))
      (node (ref "USB1") (pin "A4B9") (pinfunction "VBUS_A4B9") (pintype "unspecified"))
      (node (ref "USB1") (pin "B4A9") (pinfunction "VBUS_B4A9") (pintype "unspecified"))
    )
    (net (code "92") (name "VIN+") (class "Default")
      (node (ref "R15") (pin "1") (pinfunction "1_1") (pintype "unspecified"))
      (node (ref "SW3") (pin "2") (pinfunction "2_2") (pintype "unspecified"))
      (node (ref "U12") (pin "10") (pinfunction "VIN+_10") (pintype "unspecified"))
      (node (ref "U12") (pin "8") (pinfunction "VBUS_8") (pintype "unspecified"))
    )
    (net (code "93") (name "unconnected-(CN1-Pad11)") (class "Default")
      (node (ref "CN1") (pin "11") (pinfunction "11_11") (pintype "unspecified"))
    )
    (net (code "94") (name "unconnected-(CN1-Pad17)") (class "Default")
      (node (ref "CN1") (pin "17") (pinfunction "17_17") (pintype "unspecified"))
    )
    (net (code "95") (name "unconnected-(CN1-Pad19)") (class "Default")
      (node (ref "CN1") (pin "19") (pinfunction "19_19") (pintype "unspecified"))
    )
    (net (code "96") (name "unconnected-(H1-Pad1)") (class "Default")
      (node (ref "H1") (pin "1") (pinfunction "1_1") (pintype "unspecified"))
    )
    (net (code "97") (name "unconnected-(H2-Pad2)") (class "Default")
      (node (ref "H2") (pin "2") (pinfunction "2_2") (pintype "unspecified"))
    )
    (net (code "98") (name "unconnected-(H2-Pad3)") (class "Default")
      (node (ref "H2") (pin "3") (pinfunction "3_3") (pintype "unspecified"))
    )
    (net (code "99") (name "unconnected-(H2-Pad4)") (class "Default")
      (node (ref "H2") (pin "4") (pinfunction "4_4") (pintype "unspecified"))
    )
    (net (code "100") (name "unconnected-(H4-Pad1)") (class "Default")
      (node (ref "H4") (pin "1") (pinfunction "1_1") (pintype "unspecified"))
    )
    (net (code "101") (name "unconnected-(H5-Pad1)") (class "Default")
      (node (ref "H5") (pin "1") (pinfunction "1_1") (pintype "unspecified"))
    )
    (net (code "102") (name "unconnected-(SW3-Pad5)") (class "Default")
      (node (ref "SW3") (pin "5") (pinfunction "5_5") (pintype "unspecified"))
    )
    (net (code "103") (name "unconnected-(U1-SPLIT-Pad5)") (class "Default")
      (node (ref "U1") (pin "5") (pinfunction "SPLIT_5") (pintype "unspecified"))
    )
    (net (code "104") (name "unconnected-(U6-ADC-Pad2)") (class "Default")
      (node (ref "U6") (pin "2") (pinfunction "ADC_2") (pintype "unspecified"))
    )
    (net (code "105") (name "unconnected-(U6-CS0-Pad17)") (class "Default")
      (node (ref "U6") (pin "17") (pinfunction "CS0_17") (pintype "unspecified"))
    )
    (net (code "106") (name "unconnected-(U6-GPIO2-Pad11)") (class "Default")
      (node (ref "U6") (pin "11") (pinfunction "GPIO2_11") (pintype "unspecified"))
    )
    (net (code "107") (name "unconnected-(U6-GPIO4-Pad13)") (class "Default")
      (node (ref "U6") (pin "13") (pinfunction "GPIO4_13") (pintype "unspecified"))
    )
    (net (code "108") (name "unconnected-(U6-GPIO5-Pad14)") (class "Default")
      (node (ref "U6") (pin "14") (pinfunction "GPIO5_14") (pintype "unspecified"))
    )
    (net (code "109") (name "unconnected-(U6-GPIO9-Pad19)") (class "Default")
      (node (ref "U6") (pin "19") (pinfunction "GPIO9_19") (pintype "unspecified"))
    )
    (net (code "110") (name "unconnected-(U6-GPIO10-Pad20)") (class "Default")
      (node (ref "U6") (pin "20") (pinfunction "GPIO10_20") (pintype "unspecified"))
    )
    (net (code "111") (name "unconnected-(U6-GPIO12-Pad6)") (class "Default")
      (node (ref "U6") (pin "6") (pinfunction "GPIO12_6") (pintype "unspecified"))
    )
    (net (code "112") (name "unconnected-(U6-GPIO13-Pad7)") (class "Default")
      (node (ref "U6") (pin "7") (pinfunction "GPIO13_7") (pintype "unspecified"))
    )
    (net (code "113") (name "unconnected-(U6-GPIO14-Pad5)") (class "Default")
      (node (ref "U6") (pin "5") (pinfunction "GPIO14_5") (pintype "unspecified"))
    )
    (net (code "114") (name "unconnected-(U6-GPIO16-Pad4)") (class "Default")
      (node (ref "U6") (pin "4") (pinfunction "GPIO16_4") (pintype "unspecified"))
    )
    (net (code "115") (name "unconnected-(U6-MISO-Pad18)") (class "Default")
      (node (ref "U6") (pin "18") (pinfunction "MISO_18") (pintype "unspecified"))
    )
    (net (code "116") (name "unconnected-(U6-MOSI-Pad21)") (class "Default")
      (node (ref "U6") (pin "21") (pinfunction "MOSI_21") (pintype "unspecified"))
    )
    (net (code "117") (name "unconnected-(U6-SCLK-Pad22)") (class "Default")
      (node (ref "U6") (pin "22") (pinfunction "SCLK_22") (pintype "unspecified"))
    )
    (net (code "118") (name "unconnected-(U7-NC-Pad1)") (class "Default")
      (node (ref "U7") (pin "1") (pinfunction "NC_1") (pintype "unspecified"))
    )
    (net (code "119") (name "unconnected-(U7-NC-Pad6)") (class "Default")
      (node (ref "U7") (pin "6") (pinfunction "NC_6") (pintype "unspecified"))
    )
    (net (code "120") (name "unconnected-(U9-N.C.-Pad7)") (class "Default")
      (node (ref "U9") (pin "7") (pinfunction "N.C._7") (pintype "unspecified"))
    )
    (net (code "121") (name "unconnected-(U10-CTS#-Pad9)") (class "Default")
      (node (ref "U10") (pin "9") (pinfunction "CTS#_9") (pintype "unspecified"))
    )
    (net (code "122") (name "unconnected-(U10-DCD#-Pad12)") (class "Default")
      (node (ref "U10") (pin "12") (pinfunction "DCD#_12") (pintype "unspecified"))
    )
    (net (code "123") (name "unconnected-(U10-DSR#-Pad10)") (class "Default")
      (node (ref "U10") (pin "10") (pinfunction "DSR#_10") (pintype "unspecified"))
    )
    (net (code "124") (name "unconnected-(U10-DTR#-Pad13)") (class "Default")
      (node (ref "U10") (pin "13") (pinfunction "DTR#_13") (pintype "unspecified"))
    )
    (net (code "125") (name "unconnected-(U10-R232-Pad15)") (class "Default")
      (node (ref "U10") (pin "15") (pinfunction "R232_15") (pintype "unspecified"))
    )
    (net (code "126") (name "unconnected-(U10-RI#-Pad11)") (class "Default")
      (node (ref "U10") (pin "11") (pinfunction "RI#_11") (pintype "unspecified"))
    )
    (net (code "127") (name "unconnected-(U10-RTS#-Pad14)") (class "Default")
      (node (ref "U10") (pin "14") (pinfunction "RTS#_14") (pintype "unspecified"))
    )
    (net (code "128") (name "unconnected-(U10-UD+-Pad5)") (class "Default")
      (node (ref "U10") (pin "5") (pinfunction "UD+_5") (pintype "unspecified"))
    )
    (net (code "129") (name "unconnected-(U10-UD--Pad6)") (class "Default")
      (node (ref "U10") (pin "6") (pinfunction "UD-_6") (pintype "unspecified"))
    )
    (net (code "130") (name "unconnected-(U11-VOUT-Pad2)") (class "Default")
      (node (ref "U11") (pin "2") (pinfunction "VOUT_2") (pintype "unspecified"))
    )
    (net (code "131") (name "unconnected-(U12-Alert-Pad3)") (class "Default")
      (node (ref "U12") (pin "3") (pinfunction "Alert_3") (pintype "unspecified"))
    )
    (net (code "132") (name "unconnected-(USB1-CC1-PadA5)") (class "Default")
      (node (ref "USB1") (pin "A5") (pinfunction "CC1_A5") (pintype "unspecified"))
    )
    (net (code "133") (name "unconnected-(USB1-CC2-PadB5)") (class "Default")
      (node (ref "USB1") (pin "B5") (pinfunction "CC2_B5") (pintype "unspecified"))
    )
    (net (code "134") (name "unconnected-(USB1-SBU1-PadA8)") (class "Default")
      (node (ref "USB1") (pin "A8") (pinfunction "SBU1_A8") (pintype "unspecified"))
    )
    (net (code "135") (name "unconnected-(USB1-SBU2-PadB8)") (class "Default")
      (node (ref "USB1") (pin "B8") (pinfunction "SBU2_B8") (pintype "unspecified"))
    )
    (net (code "136") (name "unconnected-(X1-Pad1)") (class "Default")
      (node (ref "X1") (pin "1") (pinfunction "1_1") (pintype "input"))
    )
  )
)
